# EEZ_DIB_AFE3_r1B2.net
KiCad netlist of a schematic drawn in EAGLE
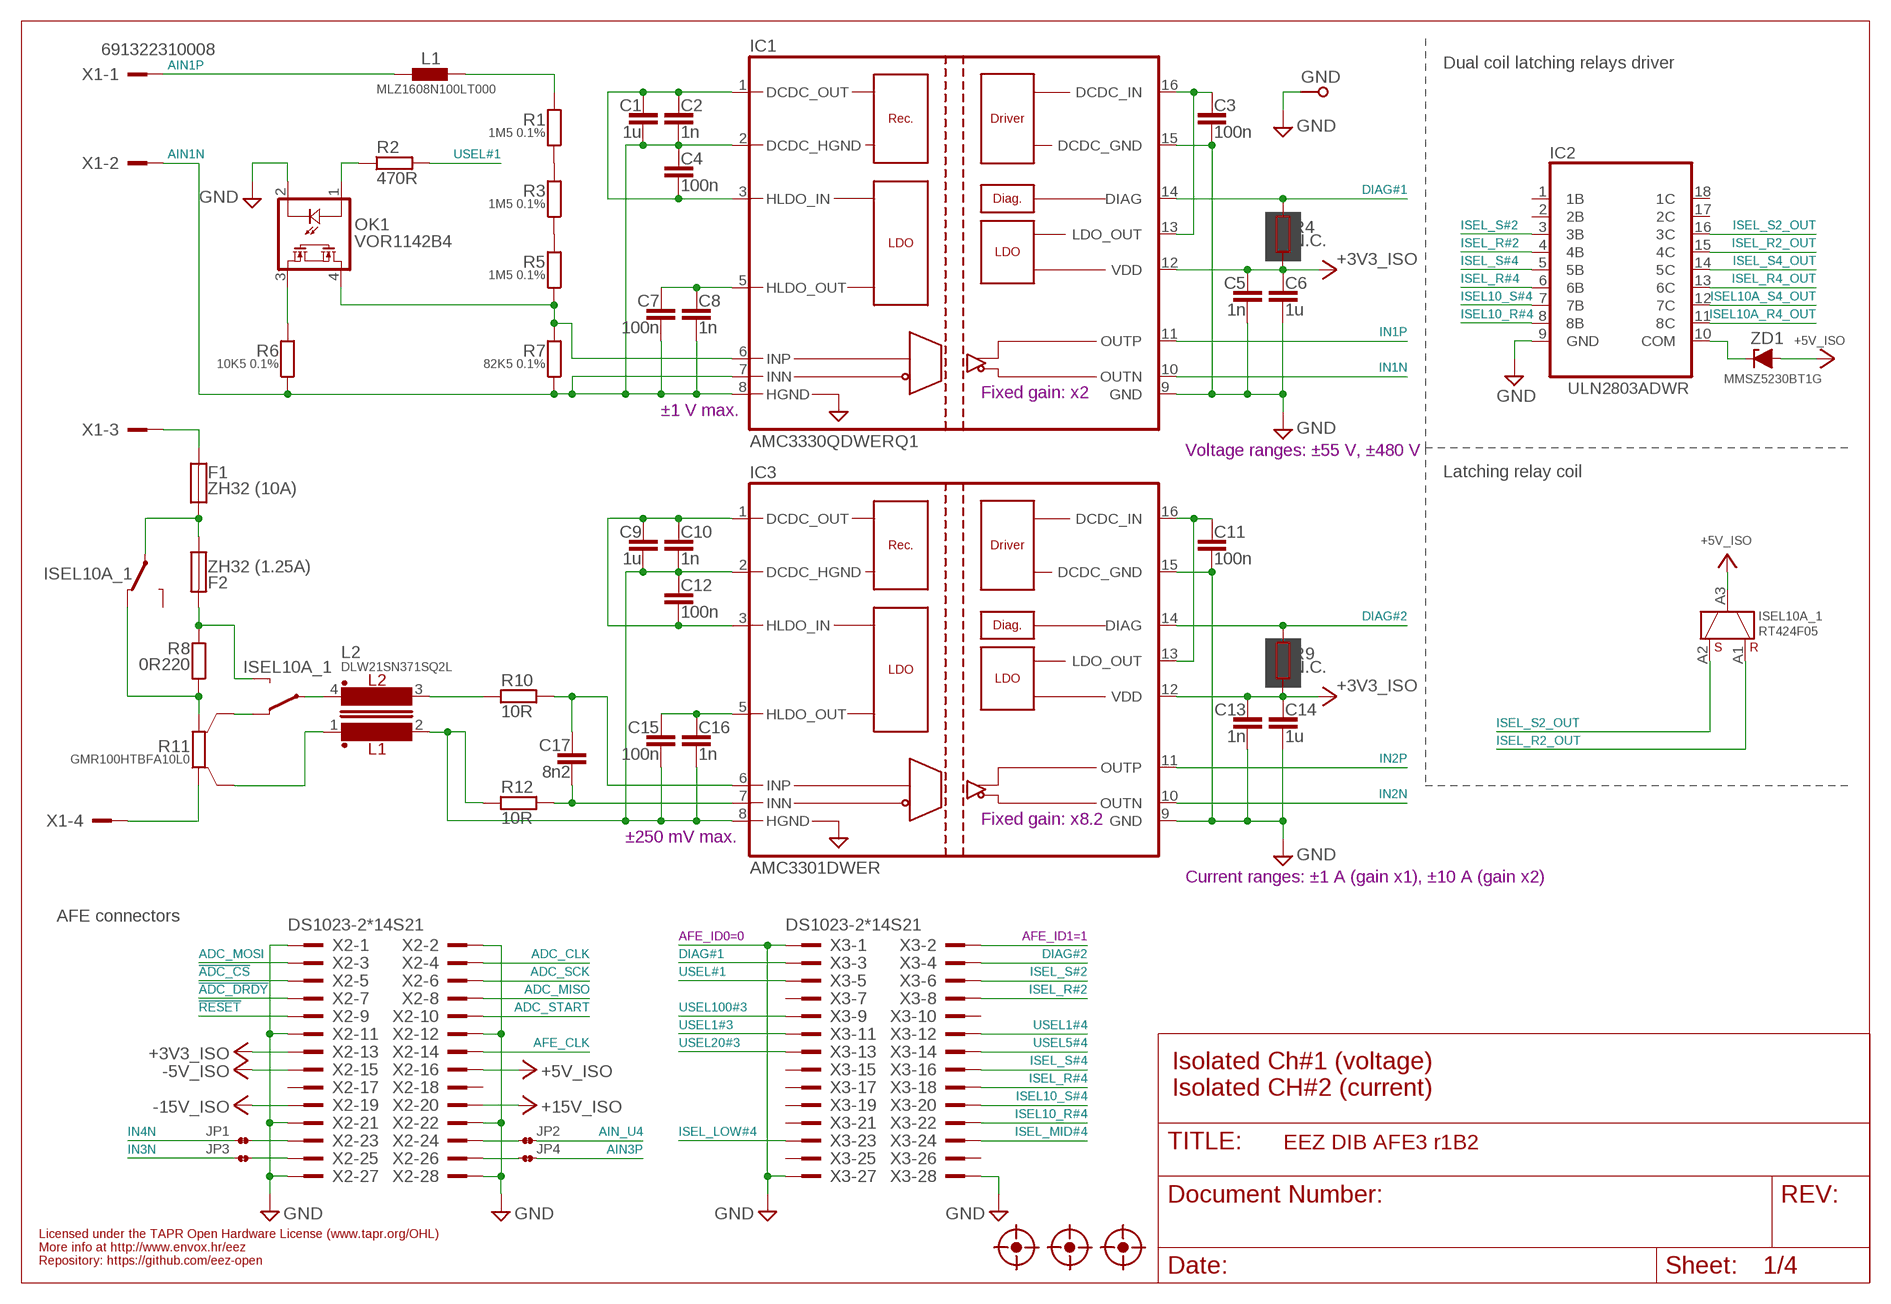
[diagram p0: schematic, sheet 1]
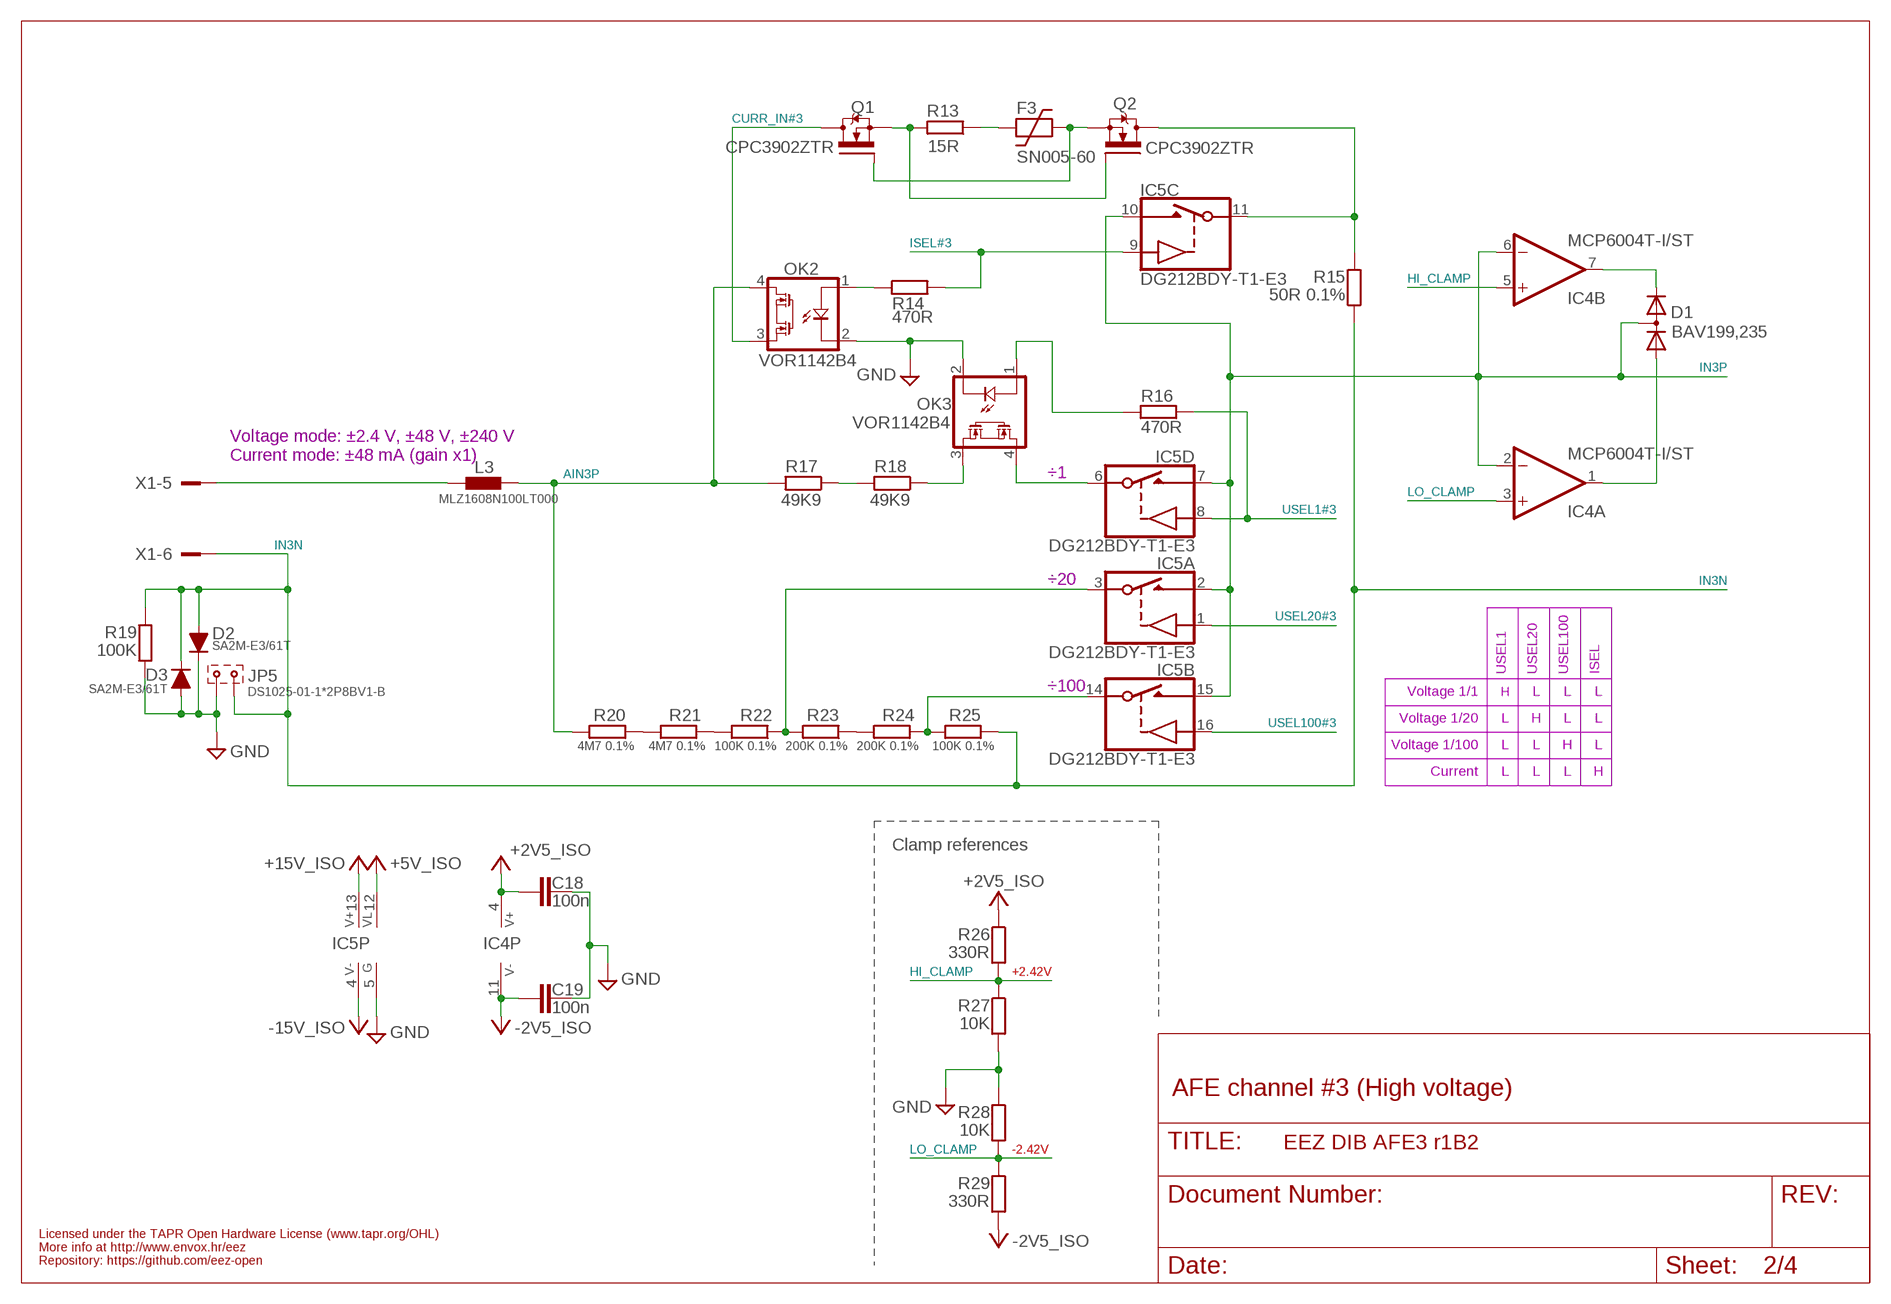
[diagram p1: schematic, sheet 2]
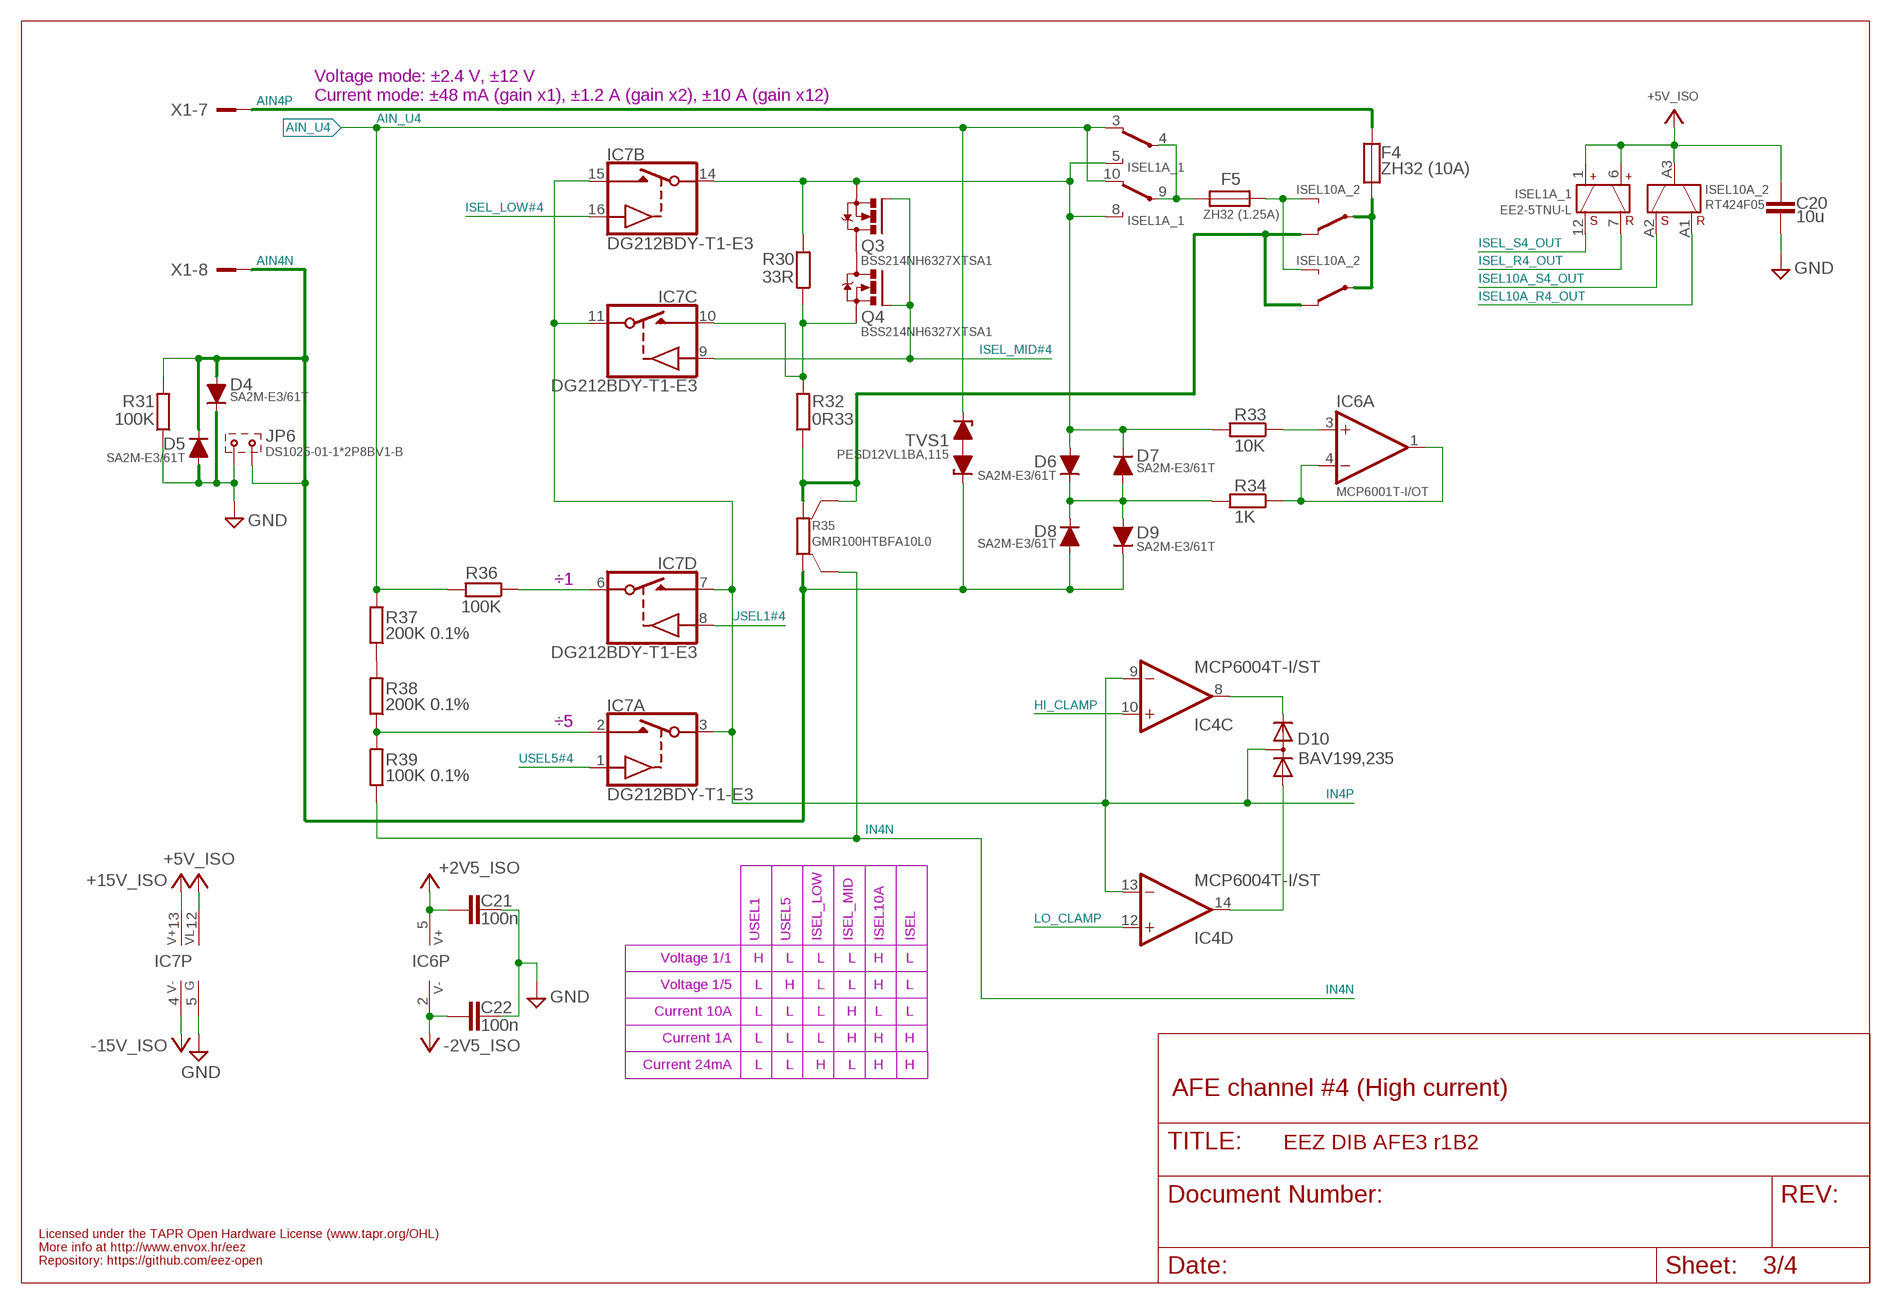
[diagram p2: schematic, sheet 3]
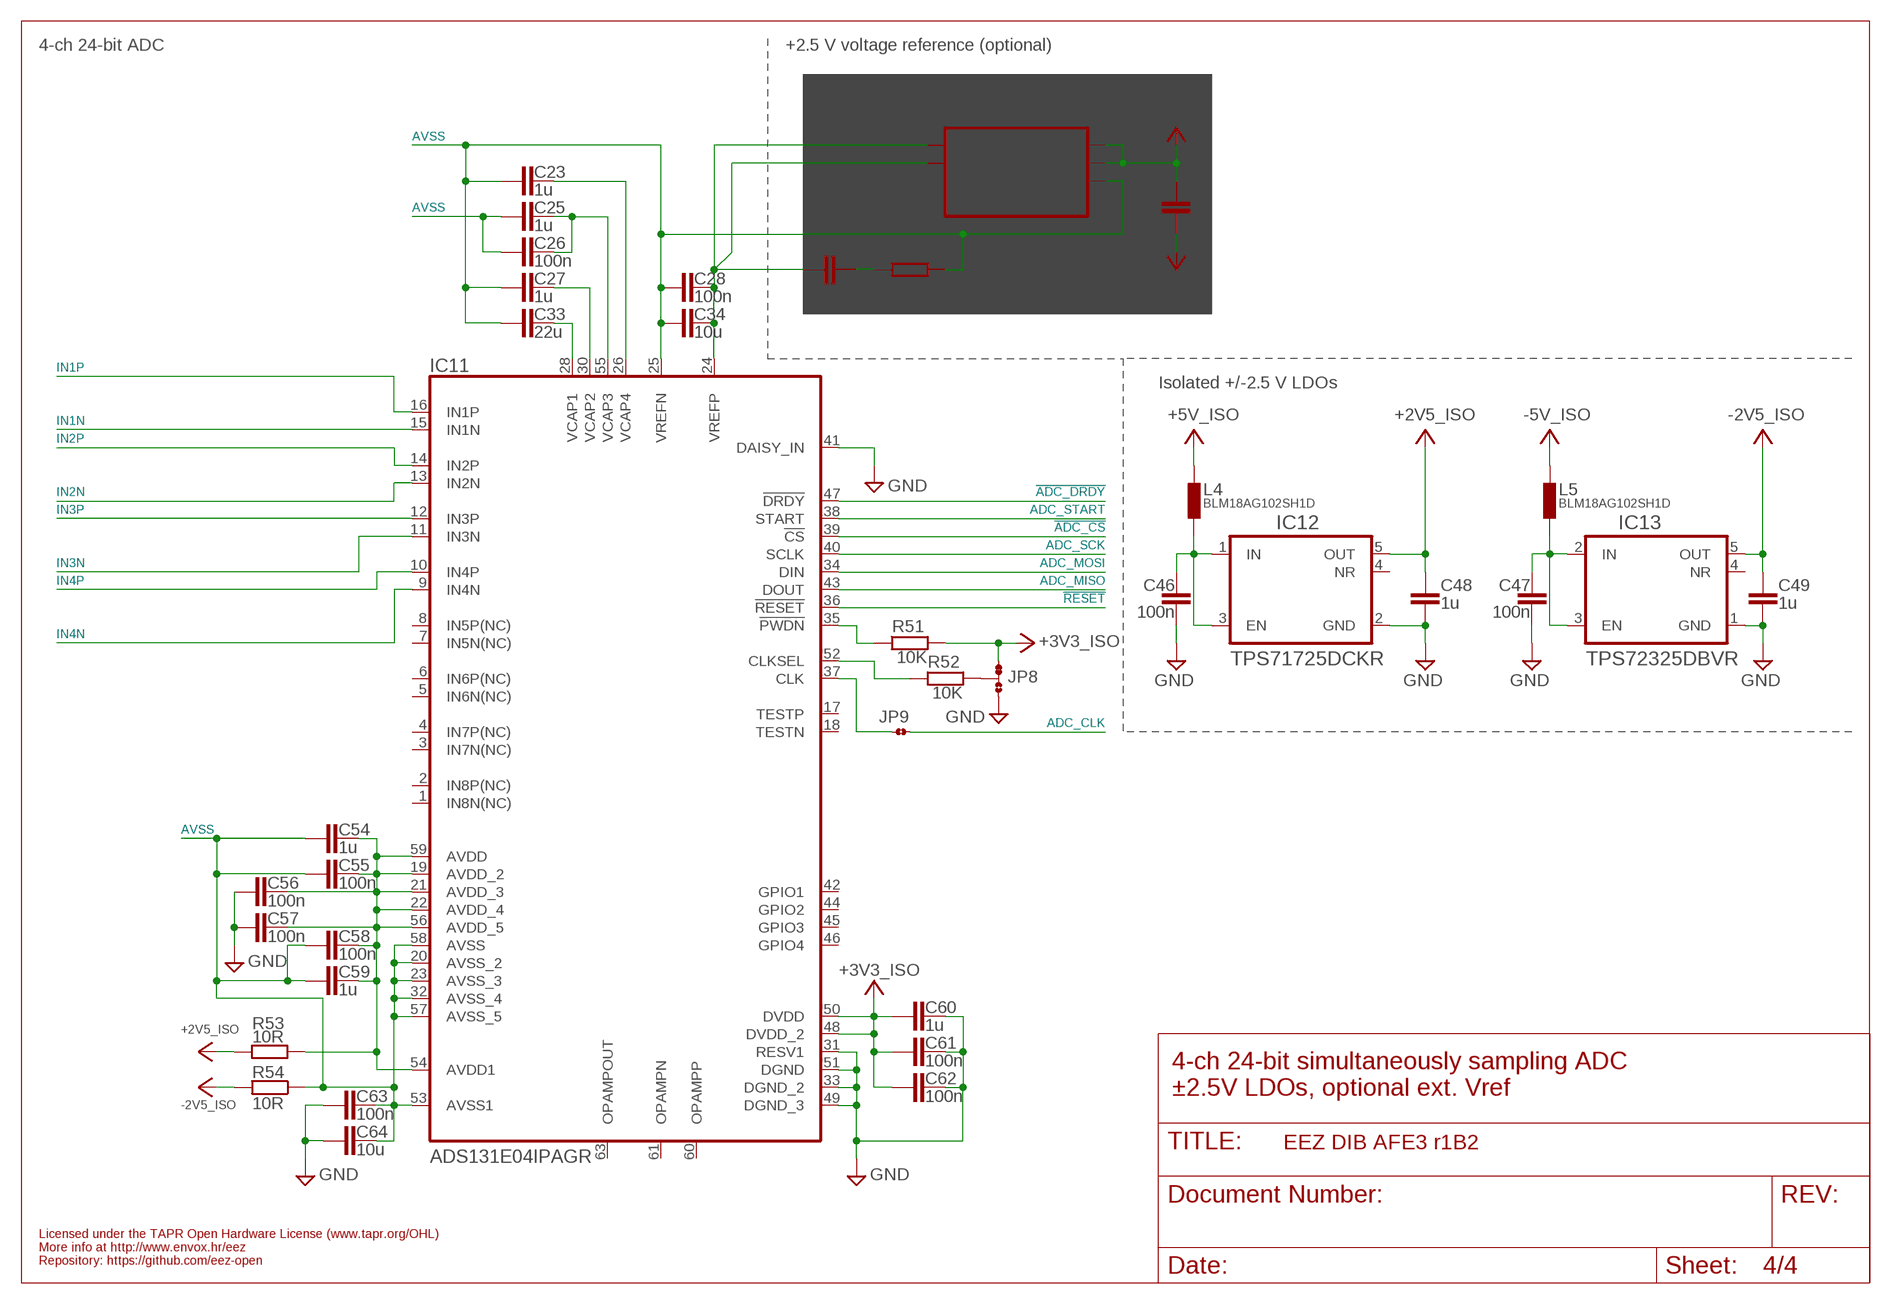
[diagram p3: schematic, sheet 4]

(export (version "E")
  (design (tool "Eeschema 10.0.6"))
  (components
    (comp (ref "C18")
      (value "100n")
      (footprint "eagle-import:C0603")
      (libsource (lib "eagle-import") (part "C-EUC0603"))
    )
    (comp (ref "C19")
      (value "100n")
      (footprint "eagle-import:C0603")
      (libsource (lib "eagle-import") (part "C-EUC0603"))
    )
    (comp (ref "D1")
      (value "BAV199,235")
      (footprint "eagle-import:SOT23")
      (libsource (lib "eagle-import") (part "BAV199"))
    )
    (comp (ref "D2")
      (value "SA2M-E3/61T")
      (footprint "eagle-import:SMA_NARROW")
      (libsource (lib "eagle-import") (part "DIODE_SMA-NARROW"))
    )
    (comp (ref "D3")
      (value "SA2M-E3/61T")
      (footprint "eagle-import:SMA_NARROW")
      (libsource (lib "eagle-import") (part "DIODE_SMA-NARROW"))
    )
    (comp (ref "F3")
      (value "SN005-60")
      (footprint "eagle-import:C1206-HV")
      (libsource (lib "eagle-import") (part "FUSE_RESETTABLE2"))
    )
    (comp (ref "IC4")
      (value "MCP6004T-I/ST")
      (footprint "eagle-import:PW(R-PDSO-G14)")
      (libsource (lib "eagle-import") (part "OPA4197PW"))
    )
    (comp (ref "IC5")
      (value "DG212BDY-T1-E3")
      (footprint "eagle-import:SO16")
      (libsource (lib "eagle-import") (part "DG212BDY-T1-E3"))
    )
    (comp (ref "JP5")
      (value "DS1025-01-1*2P8BV1-B")
      (footprint "eagle-import:2MM-2")
      (libsource (lib "eagle-import") (part "JUMPER-2PIN-2MM"))
    )
    (comp (ref "L3")
      (value "MLZ1608N100LT000")
      (footprint "eagle-import:BEAD0603")
      (libsource (lib "eagle-import") (part "FERRITE_BEAD0603"))
    )
    (comp (ref "OK2")
      (value "VOR1142B4")
      (footprint "eagle-import:DIL4-SMD")
      (libsource (lib "eagle-import") (part "VOR1142B4"))
    )
    (comp (ref "OK3")
      (value "VOR1142B4")
      (footprint "eagle-import:DIL4-SMD")
      (libsource (lib "eagle-import") (part "VOR1142B4"))
    )
    (comp (ref "Q1")
      (value "CPC3902ZTR")
      (footprint "eagle-import:SOT230P700X180-4N")
      (libsource (lib "eagle-import") (part "BSP129SOT-223"))
    )
    (comp (ref "Q2")
      (value "CPC3902ZTR")
      (footprint "eagle-import:SOT230P700X180-4N")
      (libsource (lib "eagle-import") (part "BSP129SOT-223"))
    )
    (comp (ref "R13")
      (value "15R")
      (footprint "eagle-import:R0805")
      (libsource (lib "eagle-import") (part "R-EU_R0805"))
    )
    (comp (ref "R14")
      (value "470R")
      (footprint "eagle-import:R0805")
      (libsource (lib "eagle-import") (part "R-EU_R0805"))
    )
    (comp (ref "R15")
      (value "50R 0.1%")
      (footprint "eagle-import:R1206")
      (libsource (lib "eagle-import") (part "R-EU_R1206"))
    )
    (comp (ref "R16")
      (value "470R")
      (footprint "eagle-import:R0805")
      (libsource (lib "eagle-import") (part "R-EU_R0805"))
    )
    (comp (ref "R17")
      (value "49K9")
      (footprint "eagle-import:R1206")
      (libsource (lib "eagle-import") (part "R-EU_R1206"))
    )
    (comp (ref "R18")
      (value "49K9")
      (footprint "eagle-import:R1206")
      (libsource (lib "eagle-import") (part "R-EU_R1206"))
    )
    (comp (ref "R19")
      (value "100K")
      (footprint "eagle-import:R1206")
      (libsource (lib "eagle-import") (part "R-EU_R1206"))
    )
    (comp (ref "R20")
      (value "4M7 0.1%")
      (footprint "eagle-import:R1206")
      (libsource (lib "eagle-import") (part "R-EU_R1206"))
    )
    (comp (ref "R21")
      (value "4M7 0.1%")
      (footprint "eagle-import:R1206")
      (libsource (lib "eagle-import") (part "R-EU_R1206"))
    )
    (comp (ref "R22")
      (value "100K 0.1%")
      (footprint "eagle-import:R1206")
      (libsource (lib "eagle-import") (part "R-EU_R1206"))
    )
    (comp (ref "R23")
      (value "200K 0.1%")
      (footprint "eagle-import:R1206")
      (libsource (lib "eagle-import") (part "R-EU_R1206"))
    )
    (comp (ref "R24")
      (value "200K 0.1%")
      (footprint "eagle-import:R1206")
      (libsource (lib "eagle-import") (part "R-EU_R1206"))
    )
    (comp (ref "R25")
      (value "100K 0.1%")
      (footprint "eagle-import:R1206")
      (libsource (lib "eagle-import") (part "R-EU_R1206"))
    )
    (comp (ref "R26")
      (value "330R")
      (footprint "eagle-import:R0805")
      (libsource (lib "eagle-import") (part "R-EU_R0805"))
    )
    (comp (ref "R27")
      (value "10K")
      (footprint "eagle-import:R0805")
      (libsource (lib "eagle-import") (part "R-EU_R0805"))
    )
    (comp (ref "R28")
      (value "10K")
      (footprint "eagle-import:R0805")
      (libsource (lib "eagle-import") (part "R-EU_R0805"))
    )
    (comp (ref "R29")
      (value "330R")
      (footprint "eagle-import:R0805")
      (libsource (lib "eagle-import") (part "R-EU_R0805"))
    )
    (comp (ref "X1")
      (value "691322310008")
      (footprint "eagle-import:691322310008")
      (libsource (lib "eagle-import") (part "691322310008"))
    )
    (comp (ref "C23")
      (value "1u")
      (footprint "eagle-import:C0805")
      (libsource (lib "eagle-import") (part "C-EUC0805"))
    )
    (comp (ref "C24")
      (value "N.C.")
      (footprint "eagle-import:C1206")
      (libsource (lib "eagle-import") (part "C-EUC1206"))
    )
    (comp (ref "C25")
      (value "1u")
      (footprint "eagle-import:C0805")
      (libsource (lib "eagle-import") (part "C-EUC0805"))
    )
    (comp (ref "C26")
      (value "100n")
      (footprint "eagle-import:C0603")
      (libsource (lib "eagle-import") (part "C-EUC0603"))
    )
    (comp (ref "C27")
      (value "1u")
      (footprint "eagle-import:C0805")
      (libsource (lib "eagle-import") (part "C-EUC0805"))
    )
    (comp (ref "C28")
      (value "100n")
      (footprint "eagle-import:C0603")
      (libsource (lib "eagle-import") (part "C-EUC0603"))
    )
    (comp (ref "C33")
      (value "22u")
      (footprint "eagle-import:C1206")
      (libsource (lib "eagle-import") (part "C-EUC1206"))
    )
    (comp (ref "C34")
      (value "10u")
      (footprint "eagle-import:C1206")
      (libsource (lib "eagle-import") (part "C-EUC1206"))
    )
    (comp (ref "C35")
      (value "N.C.")
      (footprint "eagle-import:C1206")
      (libsource (lib "eagle-import") (part "C-EUC1206"))
    )
    (comp (ref "C46")
      (value "100n")
      (footprint "eagle-import:C0603")
      (libsource (lib "eagle-import") (part "C-EUC0603"))
    )
    (comp (ref "C47")
      (value "100n")
      (footprint "eagle-import:C0603")
      (libsource (lib "eagle-import") (part "C-EUC0603"))
    )
    (comp (ref "C48")
      (value "1u")
      (footprint "eagle-import:C0805")
      (libsource (lib "eagle-import") (part "C-EUC0805"))
    )
    (comp (ref "C49")
      (value "1u")
      (footprint "eagle-import:C0805")
      (libsource (lib "eagle-import") (part "C-EUC0805"))
    )
    (comp (ref "C54")
      (value "1u")
      (footprint "eagle-import:C0805")
      (libsource (lib "eagle-import") (part "C-EUC0805"))
    )
    (comp (ref "C55")
      (value "100n")
      (footprint "eagle-import:C0603")
      (libsource (lib "eagle-import") (part "C-EUC0603"))
    )
    (comp (ref "C56")
      (value "100n")
      (footprint "eagle-import:C0603")
      (libsource (lib "eagle-import") (part "C-EUC0603"))
    )
    (comp (ref "C57")
      (value "100n")
      (footprint "eagle-import:C0603")
      (libsource (lib "eagle-import") (part "C-EUC0603"))
    )
    (comp (ref "C58")
      (value "100n")
      (footprint "eagle-import:C0603")
      (libsource (lib "eagle-import") (part "C-EUC0603"))
    )
    (comp (ref "C59")
      (value "1u")
      (footprint "eagle-import:C0805")
      (libsource (lib "eagle-import") (part "C-EUC0805"))
    )
    (comp (ref "C60")
      (value "1u")
      (footprint "eagle-import:C0805")
      (libsource (lib "eagle-import") (part "C-EUC0805"))
    )
    (comp (ref "C61")
      (value "100n")
      (footprint "eagle-import:C0603")
      (libsource (lib "eagle-import") (part "C-EUC0603"))
    )
    (comp (ref "C62")
      (value "100n")
      (footprint "eagle-import:C0603")
      (libsource (lib "eagle-import") (part "C-EUC0603"))
    )
    (comp (ref "C63")
      (value "100n")
      (footprint "eagle-import:C0603")
      (libsource (lib "eagle-import") (part "C-EUC0603"))
    )
    (comp (ref "C64")
      (value "10u")
      (footprint "eagle-import:C1206")
      (libsource (lib "eagle-import") (part "C-EUC1206"))
    )
    (comp (ref "IC8")
      (value "N.C.")
      (footprint "eagle-import:MSOP-8_MS_LIT")
      (libsource (lib "eagle-import") (part "LTC6655BHMS8"))
    )
    (comp (ref "IC11")
      (value "ADS131E04IPAGR")
      (footprint "eagle-import:PAG64")
      (libsource (lib "eagle-import") (part "ADS131E0XIPAG"))
    )
    (comp (ref "IC12")
      (value "TPS71725DCKR")
      (footprint "eagle-import:DCK5")
      (libsource (lib "eagle-import") (part "TPS71725DCKR"))
    )
    (comp (ref "IC13")
      (value "TPS72325DBVR")
      (footprint "eagle-import:DBV5")
      (libsource (lib "eagle-import") (part "TPS72325DBVR"))
    )
    (comp (ref "JP8")
      (value "JP3-CUT-0805-ROTATED")
      (footprint "eagle-import:JP3-0805-CUT2")
      (libsource (lib "eagle-import") (part "JP3-CUT-0805-ROTATED"))
    )
    (comp (ref "JP9")
      (value "JP2-CUT-0805")
      (footprint "eagle-import:R_0805")
      (libsource (lib "eagle-import") (part "JP2-CUT-0805"))
    )
    (comp (ref "L4")
      (value "BLM18AG102SH1D")
      (footprint "eagle-import:BEAD0603")
      (libsource (lib "eagle-import") (part "FERRITE_BEAD0603"))
    )
    (comp (ref "L5")
      (value "BLM18AG102SH1D")
      (footprint "eagle-import:BEAD0603")
      (libsource (lib "eagle-import") (part "FERRITE_BEAD0603"))
    )
    (comp (ref "R51")
      (value "10K")
      (footprint "eagle-import:R0805")
      (libsource (lib "eagle-import") (part "R-EU_R0805"))
    )
    (comp (ref "R52")
      (value "10K")
      (footprint "eagle-import:R0805")
      (libsource (lib "eagle-import") (part "R-EU_R0805"))
    )
    (comp (ref "R53")
      (value "10R")
      (footprint "eagle-import:R0805")
      (libsource (lib "eagle-import") (part "R-EU_R0805"))
    )
    (comp (ref "R54")
      (value "10R")
      (footprint "eagle-import:R0805")
      (libsource (lib "eagle-import") (part "R-EU_R0805"))
    )
    (comp (ref "R65")
      (value "N.C.")
      (footprint "eagle-import:R0805")
      (libsource (lib "eagle-import") (part "R-EU_R0805"))
    )
    (comp (ref "C20")
      (value "10u")
      (footprint "eagle-import:C1206")
      (libsource (lib "eagle-import") (part "C-EUC1206"))
    )
    (comp (ref "C21")
      (value "100n")
      (footprint "eagle-import:C0603")
      (libsource (lib "eagle-import") (part "C-EUC0603"))
    )
    (comp (ref "C22")
      (value "100n")
      (footprint "eagle-import:C0603")
      (libsource (lib "eagle-import") (part "C-EUC0603"))
    )
    (comp (ref "D4")
      (value "SA2M-E3/61T")
      (footprint "eagle-import:SMA_NARROW")
      (libsource (lib "eagle-import") (part "DIODE_SMA-NARROW"))
    )
    (comp (ref "D5")
      (value "SA2M-E3/61T")
      (footprint "eagle-import:SMA_NARROW")
      (libsource (lib "eagle-import") (part "DIODE_SMA-NARROW"))
    )
    (comp (ref "D6")
      (value "SA2M-E3/61T")
      (footprint "eagle-import:SMA_NARROW")
      (libsource (lib "eagle-import") (part "DIODE_SMA-NARROW"))
    )
    (comp (ref "D7")
      (value "SA2M-E3/61T")
      (footprint "eagle-import:SMA_NARROW")
      (libsource (lib "eagle-import") (part "DIODE_SMA-NARROW"))
    )
    (comp (ref "D8")
      (value "SA2M-E3/61T")
      (footprint "eagle-import:SMA_NARROW")
      (libsource (lib "eagle-import") (part "DIODE_SMA-NARROW"))
    )
    (comp (ref "D9")
      (value "SA2M-E3/61T")
      (footprint "eagle-import:SMA_NARROW")
      (libsource (lib "eagle-import") (part "DIODE_SMA-NARROW"))
    )
    (comp (ref "D10")
      (value "BAV199,235")
      (footprint "eagle-import:SOT23")
      (libsource (lib "eagle-import") (part "BAV199"))
    )
    (comp (ref "F4")
      (value "ZH32 (10A)")
      (footprint "eagle-import:ZH32")
      (libsource (lib "eagle-import") (part "ZH32"))
    )
    (comp (ref "F5")
      (value "ZH32 (1.25A)")
      (footprint "eagle-import:ZH32")
      (libsource (lib "eagle-import") (part "ZH32"))
    )
    (comp (ref "IC6")
      (value "MCP6001T-I/OT")
      (footprint "eagle-import:DBV5")
      (libsource (lib "eagle-import") (part "OPA376AIDBVR"))
    )
    (comp (ref "IC7")
      (value "DG212BDY-T1-E3")
      (footprint "eagle-import:SO16")
      (libsource (lib "eagle-import") (part "DG212BDY-T1-E3"))
    )
    (comp (ref "ISEL1A_1")
      (value "EE2-5TNU-L")
      (footprint "eagle-import:G6SK-2F")
      (libsource (lib "eagle-import") (part "G6SK-2F"))
    )
    (comp (ref "ISEL10A_2")
      (value "RT424F05")
      (footprint "eagle-import:RT424FXX")
      (libsource (lib "eagle-import") (part "RT424FXX"))
    )
    (comp (ref "JP6")
      (value "DS1025-01-1*2P8BV1-B")
      (footprint "eagle-import:2MM-2")
      (libsource (lib "eagle-import") (part "JUMPER-2PIN-2MM"))
    )
    (comp (ref "Q3")
      (value "BSS214NH6327XTSA1")
      (footprint "eagle-import:SOT103P240X110-3N")
      (fields
        (field (name "MPN") "2N7002-7-F")
        (field (name "MPN_1") "2N7002-7-F")
        (field (name "OC_FARNELL") "1713823")
        (field (name "OC_NEWARK") "25R5679")
        (field (name "PACKAGE") "SOT-23-3")
        (field (name "SUPPLIER") "DIODES INC.")
      )
      (libsource (lib "eagle-import") (part "2N7002"))
    )
    (comp (ref "Q4")
      (value "BSS214NH6327XTSA1")
      (footprint "eagle-import:SOT103P240X110-3N")
      (fields (field (name "MPN") "2N7002-7-F"))
      (libsource (lib "eagle-import") (part "2N7002"))
    )
    (comp (ref "R30")
      (value "33R")
      (footprint "eagle-import:R1206")
      (libsource (lib "eagle-import") (part "R-EU_R1206"))
    )
    (comp (ref "R31")
      (value "100K")
      (footprint "eagle-import:R1206")
      (libsource (lib "eagle-import") (part "R-EU_R1206"))
    )
    (comp (ref "R32")
      (value "0R33")
      (footprint "eagle-import:R1210")
      (libsource (lib "eagle-import") (part "R-EU_R1210"))
    )
    (comp (ref "R33")
      (value "10K")
      (footprint "eagle-import:R0805")
      (libsource (lib "eagle-import") (part "R-EU_R0805"))
    )
    (comp (ref "R34")
      (value "1K")
      (footprint "eagle-import:R0805")
      (libsource (lib "eagle-import") (part "R-EU_R0805"))
    )
    (comp (ref "R35")
      (value "GMR100HTBFA10L0")
      (footprint "eagle-import:R_2512-4WIRE")
      (libsource (lib "eagle-import") (part "R-EU_4WIRE2512"))
    )
    (comp (ref "R36")
      (value "100K")
      (footprint "eagle-import:R1206")
      (libsource (lib "eagle-import") (part "R-EU_R1206"))
    )
    (comp (ref "R37")
      (value "200K 0.1%")
      (footprint "eagle-import:R1206")
      (libsource (lib "eagle-import") (part "R-EU_R1206"))
    )
    (comp (ref "R38")
      (value "200K 0.1%")
      (footprint "eagle-import:R1206")
      (libsource (lib "eagle-import") (part "R-EU_R1206"))
    )
    (comp (ref "R39")
      (value "100K 0.1%")
      (footprint "eagle-import:R1206")
      (libsource (lib "eagle-import") (part "R-EU_R1206"))
    )
    (comp (ref "TVS1")
      (value "PESD12VL1BA,115")
      (footprint "eagle-import:SOD323-BIDIR")
      (libsource (lib "eagle-import") (part "PESDXL1BA"))
    )
    (comp (ref "C1")
      (value "1u")
      (footprint "eagle-import:C0603")
      (libsource (lib "eagle-import") (part "C-EUC0603"))
    )
    (comp (ref "C2")
      (value "1n")
      (footprint "eagle-import:C0603")
      (libsource (lib "eagle-import") (part "C-EUC0603"))
    )
    (comp (ref "C3")
      (value "100n")
      (footprint "eagle-import:C0603")
      (libsource (lib "eagle-import") (part "C-EUC0603"))
    )
    (comp (ref "C4")
      (value "100n")
      (footprint "eagle-import:C0603")
      (libsource (lib "eagle-import") (part "C-EUC0603"))
    )
    (comp (ref "C5")
      (value "1n")
      (footprint "eagle-import:C1206")
      (libsource (lib "eagle-import") (part "C-EUC1206"))
    )
    (comp (ref "C6")
      (value "1u")
      (footprint "eagle-import:C1206")
      (libsource (lib "eagle-import") (part "C-EUC1206"))
    )
    (comp (ref "C7")
      (value "100n")
      (footprint "eagle-import:C1206")
      (libsource (lib "eagle-import") (part "C-EUC1206"))
    )
    (comp (ref "C8")
      (value "1n")
      (footprint "eagle-import:C1206")
      (libsource (lib "eagle-import") (part "C-EUC1206"))
    )
    (comp (ref "C9")
      (value "1u")
      (footprint "eagle-import:C0603")
      (libsource (lib "eagle-import") (part "C-EUC0603"))
    )
    (comp (ref "C10")
      (value "1n")
      (footprint "eagle-import:C0603")
      (libsource (lib "eagle-import") (part "C-EUC0603"))
    )
    (comp (ref "C11")
      (value "100n")
      (footprint "eagle-import:C0603")
      (libsource (lib "eagle-import") (part "C-EUC0603"))
    )
    (comp (ref "C12")
      (value "100n")
      (footprint "eagle-import:C0603")
      (libsource (lib "eagle-import") (part "C-EUC0603"))
    )
    (comp (ref "C13")
      (value "1n")
      (footprint "eagle-import:C1206")
      (libsource (lib "eagle-import") (part "C-EUC1206"))
    )
    (comp (ref "C14")
      (value "1u")
      (footprint "eagle-import:C1206")
      (libsource (lib "eagle-import") (part "C-EUC1206"))
    )
    (comp (ref "C15")
      (value "100n")
      (footprint "eagle-import:C1206")
      (libsource (lib "eagle-import") (part "C-EUC1206"))
    )
    (comp (ref "C16")
      (value "1n")
      (footprint "eagle-import:C1206")
      (libsource (lib "eagle-import") (part "C-EUC1206"))
    )
    (comp (ref "C17")
      (value "8n2")
      (footprint "eagle-import:C0603")
      (libsource (lib "eagle-import") (part "C-EUC0603"))
    )
    (comp (ref "F1")
      (value "ZH32 (10A)")
      (footprint "eagle-import:ZH32")
      (libsource (lib "eagle-import") (part "ZH32"))
    )
    (comp (ref "F2")
      (value "ZH32 (1.25A)")
      (footprint "eagle-import:ZH32")
      (libsource (lib "eagle-import") (part "ZH32"))
    )
    (comp (ref "FM1")
      (value "FIDUCIAL_2")
      (footprint "eagle-import:FIDUCIAL_DUAL")
      (libsource (lib "eagle-import") (part "FIDUCIAL_2"))
    )
    (comp (ref "FM2")
      (value "FIDUCIAL_2")
      (footprint "eagle-import:FIDUCIAL_DUAL")
      (libsource (lib "eagle-import") (part "FIDUCIAL_2"))
    )
    (comp (ref "FM3")
      (value "FIDUCIAL_2")
      (footprint "eagle-import:FIDUCIAL_DUAL")
      (libsource (lib "eagle-import") (part "FIDUCIAL_2"))
    )
    (comp (ref "GND")
      (value "PCB_TEST_TABSHIELD")
      (footprint "eagle-import:PCB_SHIELD_TAB")
      (libsource (lib "eagle-import") (part "PCB_TEST_TABSHIELD"))
    )
    (comp (ref "IC1")
      (value "AMC3330QDWERQ1")
      (footprint "eagle-import:DW16")
      (libsource (lib "eagle-import") (part "AMC3301DWER"))
    )
    (comp (ref "IC2")
      (value "ULN2803ADWR")
      (footprint "eagle-import:DW18_TEX-M")
      (libsource (lib "eagle-import") (part "ULN2803ADWR"))
    )
    (comp (ref "IC3")
      (value "AMC3301DWER")
      (footprint "eagle-import:DW16")
      (libsource (lib "eagle-import") (part "AMC3301DWER"))
    )
    (comp (ref "ISEL10A_1")
      (value "RT424F05")
      (footprint "eagle-import:RT424FXX")
      (libsource (lib "eagle-import") (part "RT424FXX"))
    )
    (comp (ref "JP1")
      (value "JP2-NOCUT-0805")
      (footprint "eagle-import:JP2-0805-NOCUT")
      (libsource (lib "eagle-import") (part "JP2-NOCUT-0805"))
    )
    (comp (ref "JP2")
      (value "JP2-NOCUT-0805")
      (footprint "eagle-import:JP2-0805-NOCUT")
      (libsource (lib "eagle-import") (part "JP2-NOCUT-0805"))
    )
    (comp (ref "JP3")
      (value "JP2-NOCUT-0805")
      (footprint "eagle-import:JP2-0805-NOCUT")
      (libsource (lib "eagle-import") (part "JP2-NOCUT-0805"))
    )
    (comp (ref "JP4")
      (value "JP2-NOCUT-0805")
      (footprint "eagle-import:JP2-0805-NOCUT")
      (libsource (lib "eagle-import") (part "JP2-NOCUT-0805"))
    )
    (comp (ref "L1")
      (value "MLZ1608N100LT000")
      (footprint "eagle-import:BEAD0603")
      (libsource (lib "eagle-import") (part "FERRITE_BEAD0603"))
    )
    (comp (ref "L2")
      (value "DLW21SN371SQ2L")
      (footprint "eagle-import:MURATA_DLW21S")
      (libsource (lib "eagle-import") (part "DLW21S"))
    )
    (comp (ref "OK1")
      (value "VOR1142B4")
      (footprint "eagle-import:DIL4-SMD")
      (libsource (lib "eagle-import") (part "VOR1142B4"))
    )
    (comp (ref "R1")
      (value "1M5 0.1%")
      (footprint "eagle-import:R1206")
      (libsource (lib "eagle-import") (part "R-EU_R1206"))
    )
    (comp (ref "R2")
      (value "470R")
      (footprint "eagle-import:R0805")
      (libsource (lib "eagle-import") (part "R-EU_R0805"))
    )
    (comp (ref "R3")
      (value "1M5 0.1%")
      (footprint "eagle-import:R1206")
      (libsource (lib "eagle-import") (part "R-EU_R1206"))
    )
    (comp (ref "R4")
      (value "N.C.")
      (footprint "eagle-import:R0805")
      (libsource (lib "eagle-import") (part "R-EU_R0805"))
    )
    (comp (ref "R5")
      (value "1M5 0.1%")
      (footprint "eagle-import:R1206")
      (libsource (lib "eagle-import") (part "R-EU_R1206"))
    )
    (comp (ref "R6")
      (value "10K5 0.1%")
      (footprint "eagle-import:R1206")
      (libsource (lib "eagle-import") (part "R-EU_R1206"))
    )
    (comp (ref "R7")
      (value "82K5 0.1%")
      (footprint "eagle-import:R1206")
      (libsource (lib "eagle-import") (part "R-EU_R1206"))
    )
    (comp (ref "R8")
      (value "0R220")
      (footprint "eagle-import:R1210")
      (libsource (lib "eagle-import") (part "R-EU_R1210"))
    )
    (comp (ref "R9")
      (value "N.C.")
      (footprint "eagle-import:R0805")
      (libsource (lib "eagle-import") (part "R-EU_R0805"))
    )
    (comp (ref "R10")
      (value "10R")
      (footprint "eagle-import:R0805")
      (libsource (lib "eagle-import") (part "R-EU_R0805"))
    )
    (comp (ref "R11")
      (value "GMR100HTBFA10L0")
      (footprint "eagle-import:R_2512-4WIRE")
      (libsource (lib "eagle-import") (part "R-EU_4WIRE2512"))
    )
    (comp (ref "R12")
      (value "10R")
      (footprint "eagle-import:R0805")
      (libsource (lib "eagle-import") (part "R-EU_R0805"))
    )
    (comp (ref "X2")
      (value "DS1023-2*14S21")
      (footprint "eagle-import:TSW-114-07-F-D")
      (libsource (lib "eagle-import") (part "TSW-114-07-F-D"))
    )
    (comp (ref "X3")
      (value "DS1023-2*14S21")
      (footprint "eagle-import:TSW-114-07-F-D")
      (libsource (lib "eagle-import") (part "TSW-114-07-F-D"))
    )
    (comp (ref "ZD1")
      (value "MMSZ5230BT1G")
      (footprint "eagle-import:SOD123")
      (libsource (lib "eagle-import") (part "ZENER-DIODESOD123"))
    )
  )
  (nets
    (net (code "1") (name "+2V5_ISO") (class "Default")
      (node (ref "C18") (pin "2") (pinfunction "2_2") (pintype "passive"))
      (node (ref "C21") (pin "2") (pinfunction "2_2") (pintype "passive"))
      (node (ref "C48") (pin "2") (pinfunction "2_2") (pintype "passive"))
      (node (ref "IC12") (pin "5") (pinfunction "OUT_5") (pintype "passive"))
      (node (ref "IC4") (pin "4") (pinfunction "V+_4") (pintype "power_in"))
      (node (ref "IC6") (pin "5") (pinfunction "V+_5") (pintype "power_in"))
      (node (ref "R26") (pin "1") (pinfunction "1_1") (pintype "passive"))
      (node (ref "R53") (pin "1") (pinfunction "1_1") (pintype "passive"))
    )
    (net (code "2") (name "+3V3_ISO") (class "Default")
      (node (ref "C13") (pin "1") (pinfunction "1_1") (pintype "passive"))
      (node (ref "C14") (pin "1") (pinfunction "1_1") (pintype "passive"))
      (node (ref "C5") (pin "1") (pinfunction "1_1") (pintype "passive"))
      (node (ref "C6") (pin "1") (pinfunction "1_1") (pintype "passive"))
      (node (ref "C60") (pin "1") (pinfunction "1_1") (pintype "passive"))
      (node (ref "C61") (pin "2") (pinfunction "2_2") (pintype "passive"))
      (node (ref "C62") (pin "2") (pinfunction "2_2") (pintype "passive"))
      (node (ref "IC1") (pin "12") (pinfunction "VDD_12") (pintype "passive"))
      (node (ref "IC11") (pin "48") (pinfunction "DVDD_2_48") (pintype "power_in"))
      (node (ref "IC11") (pin "50") (pinfunction "DVDD_50") (pintype "power_in"))
      (node (ref "IC3") (pin "12") (pinfunction "VDD_12") (pintype "passive"))
      (node (ref "JP8") (pin "NC") (pinfunction "NC_NC") (pintype "passive"))
      (node (ref "R4") (pin "2") (pinfunction "2_2") (pintype "passive"))
      (node (ref "R51") (pin "2") (pinfunction "2_2") (pintype "passive"))
      (node (ref "R9") (pin "2") (pinfunction "2_2") (pintype "passive"))
      (node (ref "X2") (pin "13") (pinfunction "1_13") (pintype "passive"))
    )
    (net (code "3") (name "+5V_ISO") (class "Default")
      (node (ref "C20") (pin "1") (pinfunction "1_1") (pintype "passive"))
      (node (ref "C24") (pin "1") (pinfunction "1_1") (pintype "passive"))
      (node (ref "IC5") (pin "12") (pinfunction "VL_12") (pintype "power_in"))
      (node (ref "IC7") (pin "12") (pinfunction "VL_12") (pintype "power_in"))
      (node (ref "IC8") (pin "1") (pinfunction "~{SHDN}_1") (pintype "input"))
      (node (ref "IC8") (pin "2") (pinfunction "VIN_2") (pintype "input"))
      (node (ref "ISEL10A_1") (pin "A3") (pinfunction "COM_A3") (pintype "passive"))
      (node (ref "ISEL10A_2") (pin "A3") (pinfunction "COM_A3") (pintype "passive"))
      (node (ref "ISEL1A_1") (pin "1") (pinfunction "S+_1") (pintype "passive"))
      (node (ref "ISEL1A_1") (pin "6") (pinfunction "R+_6") (pintype "passive"))
      (node (ref "L4") (pin "P$2") (pinfunction "2_P$2") (pintype "passive"))
      (node (ref "X2") (pin "16") (pinfunction "1_16") (pintype "passive"))
      (node (ref "ZD1") (pin "A") (pinfunction "A_A") (pintype "passive"))
    )
    (net (code "4") (name "+15V_ISO") (class "Default")
      (node (ref "IC5") (pin "13") (pinfunction "V+_13") (pintype "power_in"))
      (node (ref "IC7") (pin "13") (pinfunction "V+_13") (pintype "power_in"))
      (node (ref "X2") (pin "20") (pinfunction "1_20") (pintype "passive"))
    )
    (net (code "5") (name "-2V5_ISO") (class "Default")
      (node (ref "C19") (pin "2") (pinfunction "2_2") (pintype "passive"))
      (node (ref "C22") (pin "2") (pinfunction "2_2") (pintype "passive"))
      (node (ref "C24") (pin "2") (pinfunction "2_2") (pintype "passive"))
      (node (ref "C49") (pin "2") (pinfunction "2_2") (pintype "passive"))
      (node (ref "IC13") (pin "5") (pinfunction "OUT_5") (pintype "passive"))
      (node (ref "IC4") (pin "11") (pinfunction "V-_11") (pintype "power_in"))
      (node (ref "IC6") (pin "2") (pinfunction "V-_2") (pintype "power_in"))
      (node (ref "R29") (pin "2") (pinfunction "2_2") (pintype "passive"))
      (node (ref "R54") (pin "2") (pinfunction "2_2") (pintype "passive"))
    )
    (net (code "6") (name "-5V_ISO") (class "Default")
      (node (ref "L5") (pin "P$2") (pinfunction "2_P$2") (pintype "passive"))
      (node (ref "X2") (pin "15") (pinfunction "1_15") (pintype "passive"))
    )
    (net (code "7") (name "-15V_ISO") (class "Default")
      (node (ref "IC5") (pin "4") (pinfunction "V-_4") (pintype "power_in"))
      (node (ref "IC7") (pin "4") (pinfunction "V-_4") (pintype "power_in"))
      (node (ref "X2") (pin "19") (pinfunction "1_19") (pintype "passive"))
    )
    (net (code "8") (name "ADC_CLK") (class "Default")
      (node (ref "JP9") (pin "1") (pinfunction "1_1") (pintype "passive"))
      (node (ref "X2") (pin "4") (pinfunction "1_4") (pintype "passive"))
    )
    (net (code "9") (name "ADC_MISO") (class "Default")
      (node (ref "IC11") (pin "43") (pinfunction "DOUT_43") (pintype "output"))
      (node (ref "X2") (pin "8") (pinfunction "1_8") (pintype "passive"))
    )
    (net (code "10") (name "ADC_MOSI") (class "Default")
      (node (ref "IC11") (pin "34") (pinfunction "DIN_34") (pintype "input"))
      (node (ref "X2") (pin "3") (pinfunction "1_3") (pintype "passive"))
    )
    (net (code "11") (name "ADC_SCK") (class "Default")
      (node (ref "IC11") (pin "40") (pinfunction "SCLK_40") (pintype "input"))
      (node (ref "X2") (pin "6") (pinfunction "1_6") (pintype "passive"))
    )
    (net (code "12") (name "ADC_START") (class "Default")
      (node (ref "IC11") (pin "38") (pinfunction "START_38") (pintype "input"))
      (node (ref "X2") (pin "10") (pinfunction "1_10") (pintype "passive"))
    )
    (net (code "13") (name "AFE_CLK") (class "Default")
      (node (ref "X2") (pin "14") (pinfunction "1_14") (pintype "passive"))
    )
    (net (code "14") (name "AIN1N") (class "Default")
      (node (ref "C1") (pin "2") (pinfunction "2_2") (pintype "passive"))
      (node (ref "C2") (pin "2") (pinfunction "2_2") (pintype "passive"))
      (node (ref "C4") (pin "1") (pinfunction "1_1") (pintype "passive"))
      (node (ref "C7") (pin "2") (pinfunction "2_2") (pintype "passive"))
      (node (ref "C8") (pin "2") (pinfunction "2_2") (pintype "passive"))
      (node (ref "IC1") (pin "2") (pinfunction "DCDC_HGND_2") (pintype "passive"))
      (node (ref "IC1") (pin "7") (pinfunction "INN_7") (pintype "input"))
      (node (ref "IC1") (pin "8") (pinfunction "HGND_8") (pintype "passive"))
      (node (ref "R6") (pin "1") (pinfunction "1_1") (pintype "passive"))
      (node (ref "R7") (pin "1") (pinfunction "1_1") (pintype "passive"))
      (node (ref "X1") (pin "2") (pinfunction "1_2") (pintype "passive"))
    )
    (net (code "15") (name "AIN1P") (class "Default")
      (node (ref "L1") (pin "P$2") (pinfunction "2_P$2") (pintype "passive"))
      (node (ref "X1") (pin "1") (pinfunction "1_1") (pintype "passive"))
    )
    (net (code "16") (name "AIN3P") (class "Default")
      (node (ref "JP4") (pin "2") (pinfunction "2_2") (pintype "passive"))
      (node (ref "L3") (pin "P$1") (pinfunction "1_P$1") (pintype "passive"))
      (node (ref "OK2") (pin "4") (pinfunction "S1_4") (pintype "passive"))
      (node (ref "R17") (pin "2") (pinfunction "2_2") (pintype "passive"))
      (node (ref "R20") (pin "2") (pinfunction "2_2") (pintype "passive"))
    )
    (net (code "17") (name "AIN4N") (class "Default")
      (node (ref "D4") (pin "2") (pinfunction "A_2") (pintype "passive"))
      (node (ref "D5") (pin "1") (pinfunction "C_1") (pintype "passive"))
      (node (ref "D8") (pin "2") (pinfunction "A_2") (pintype "passive"))
      (node (ref "D9") (pin "1") (pinfunction "C_1") (pintype "passive"))
      (node (ref "JP6") (pin "1") (pinfunction "1_1") (pintype "passive"))
      (node (ref "R31") (pin "2") (pinfunction "2_2") (pintype "passive"))
      (node (ref "R35") (pin "1") (pinfunction "1_1") (pintype "passive"))
      (node (ref "TVS1") (pin "C1") (pinfunction "1_C1") (pintype "passive"))
      (node (ref "X1") (pin "8") (pinfunction "1_8") (pintype "passive"))
    )
    (net (code "18") (name "AIN4P") (class "Default")
      (node (ref "F4") (pin "2") (pinfunction "2_2") (pintype "passive"))
      (node (ref "X1") (pin "7") (pinfunction "1_7") (pintype "passive"))
    )
    (net (code "19") (name "AIN_U4") (class "Default")
      (node (ref "ISEL1A_1") (pin "10") (pinfunction "NC_10") (pintype "passive"))
      (node (ref "ISEL1A_1") (pin "3") (pinfunction "NC_3") (pintype "passive"))
      (node (ref "JP2") (pin "2") (pinfunction "2_2") (pintype "passive"))
      (node (ref "R36") (pin "2") (pinfunction "2_2") (pintype "passive"))
      (node (ref "R37") (pin "2") (pinfunction "2_2") (pintype "passive"))
      (node (ref "TVS1") (pin "C2") (pinfunction "2_C2") (pintype "passive"))
    )
    (net (code "20") (name "AVSS") (class "Default")
      (node (ref "C23") (pin "1") (pinfunction "1_1") (pintype "passive"))
      (node (ref "C25") (pin "1") (pinfunction "1_1") (pintype "passive"))
      (node (ref "C26") (pin "2") (pinfunction "2_2") (pintype "passive"))
      (node (ref "C27") (pin "1") (pinfunction "1_1") (pintype "passive"))
      (node (ref "C28") (pin "2") (pinfunction "2_2") (pintype "passive"))
      (node (ref "C33") (pin "1") (pinfunction "1_1") (pintype "passive"))
      (node (ref "C34") (pin "2") (pinfunction "2_2") (pintype "passive"))
      (node (ref "C54") (pin "1") (pinfunction "1_1") (pintype "passive"))
      (node (ref "C55") (pin "2") (pinfunction "2_2") (pintype "passive"))
      (node (ref "C58") (pin "2") (pinfunction "2_2") (pintype "passive"))
      (node (ref "C59") (pin "1") (pinfunction "1_1") (pintype "passive"))
      (node (ref "C63") (pin "1") (pinfunction "1_1") (pintype "passive"))
      (node (ref "C64") (pin "1") (pinfunction "1_1") (pintype "passive"))
      (node (ref "IC11") (pin "20") (pinfunction "AVSS_2_20") (pintype "power_in"))
      (node (ref "IC11") (pin "23") (pinfunction "AVSS_3_23") (pintype "power_in"))
      (node (ref "IC11") (pin "25") (pinfunction "VREFN_25") (pintype "input"))
      (node (ref "IC11") (pin "32") (pinfunction "AVSS_4_32") (pintype "power_in"))
      (node (ref "IC11") (pin "53") (pinfunction "AVSS1_53") (pintype "power_in"))
      (node (ref "IC11") (pin "57") (pinfunction "AVSS_5_57") (pintype "power_in"))
      (node (ref "IC11") (pin "58") (pinfunction "AVSS_58") (pintype "power_in"))
      (node (ref "IC8") (pin "3") (pinfunction "GND_3") (pintype "power_in"))
      (node (ref "IC8") (pin "4") (pinfunction "GND_4") (pintype "power_in"))
      (node (ref "IC8") (pin "5") (pinfunction "GND_5") (pintype "power_in"))
      (node (ref "IC8") (pin "8") (pinfunction "GND_8") (pintype "power_in"))
      (node (ref "R54") (pin "1") (pinfunction "1_1") (pintype "passive"))
      (node (ref "R65") (pin "2") (pinfunction "2_2") (pintype "passive"))
    )
    (net (code "21") (name "CURR_IN#3") (class "Default")
      (node (ref "OK2") (pin "3") (pinfunction "S2_3") (pintype "passive"))
      (node (ref "Q1") (pin "2") (pinfunction "D_2") (pintype "passive"))
      (node (ref "Q1") (pin "4") (pinfunction "D_4") (pintype "passive"))
    )
    (net (code "22") (name "DIAG#1") (class "Default")
      (node (ref "IC1") (pin "14") (pinfunction "DIAG_14") (pintype "output"))
      (node (ref "R4") (pin "1") (pinfunction "1_1") (pintype "passive"))
      (node (ref "X3") (pin "3") (pinfunction "1_3") (pintype "passive"))
    )
    (net (code "23") (name "DIAG#2") (class "Default")
      (node (ref "IC3") (pin "14") (pinfunction "DIAG_14") (pintype "output"))
      (node (ref "R9") (pin "1") (pinfunction "1_1") (pintype "passive"))
      (node (ref "X3") (pin "4") (pinfunction "1_4") (pintype "passive"))
    )
    (net (code "24") (name "GND") (class "Default")
      (node (ref "C11") (pin "2") (pinfunction "2_2") (pintype "passive"))
      (node (ref "C13") (pin "2") (pinfunction "2_2") (pintype "passive"))
      (node (ref "C14") (pin "2") (pinfunction "2_2") (pintype "passive"))
      (node (ref "C18") (pin "1") (pinfunction "1_1") (pintype "passive"))
      (node (ref "C19") (pin "1") (pinfunction "1_1") (pintype "passive"))
      (node (ref "C20") (pin "2") (pinfunction "2_2") (pintype "passive"))
      (node (ref "C21") (pin "1") (pinfunction "1_1") (pintype "passive"))
      (node (ref "C22") (pin "1") (pinfunction "1_1") (pintype "passive"))
      (node (ref "C3") (pin "2") (pinfunction "2_2") (pintype "passive"))
      (node (ref "C46") (pin "2") (pinfunction "2_2") (pintype "passive"))
      (node (ref "C47") (pin "2") (pinfunction "2_2") (pintype "passive"))
      (node (ref "C48") (pin "1") (pinfunction "1_1") (pintype "passive"))
      (node (ref "C49") (pin "1") (pinfunction "1_1") (pintype "passive"))
      (node (ref "C5") (pin "2") (pinfunction "2_2") (pintype "passive"))
      (node (ref "C56") (pin "2") (pinfunction "2_2") (pintype "passive"))
      (node (ref "C57") (pin "2") (pinfunction "2_2") (pintype "passive"))
      (node (ref "C6") (pin "2") (pinfunction "2_2") (pintype "passive"))
      (node (ref "C60") (pin "2") (pinfunction "2_2") (pintype "passive"))
      (node (ref "C61") (pin "1") (pinfunction "1_1") (pintype "passive"))
      (node (ref "C62") (pin "1") (pinfunction "1_1") (pintype "passive"))
      (node (ref "C63") (pin "2") (pinfunction "2_2") (pintype "passive"))
      (node (ref "C64") (pin "2") (pinfunction "2_2") (pintype "passive"))
      (node (ref "D2") (pin "1") (pinfunction "C_1") (pintype "passive"))
      (node (ref "D3") (pin "2") (pinfunction "A_2") (pintype "passive"))
      (node (ref "D4") (pin "1") (pinfunction "C_1") (pintype "passive"))
      (node (ref "D5") (pin "2") (pinfunction "A_2") (pintype "passive"))
      (node (ref "GND") (pin "1") (pinfunction "P$1_1") (pintype "bidirectional"))
      (node (ref "IC1") (pin "15") (pinfunction "DCDC_GND_15") (pintype "passive"))
      (node (ref "IC1") (pin "9") (pinfunction "GND_9") (pintype "passive"))
      (node (ref "IC11") (pin "31") (pinfunction "RESV1_31") (pintype "input"))
      (node (ref "IC11") (pin "33") (pinfunction "DGND_2_33") (pintype "power_in"))
      (node (ref "IC11") (pin "41") (pinfunction "DAISY_IN_41") (pintype "input"))
      (node (ref "IC11") (pin "49") (pinfunction "DGND_3_49") (pintype "power_in"))
      (node (ref "IC11") (pin "51") (pinfunction "DGND_51") (pintype "power_in"))
      (node (ref "IC12") (pin "2") (pinfunction "GND_2") (pintype "passive"))
      (node (ref "IC13") (pin "1") (pinfunction "GND_1") (pintype "passive"))
      (node (ref "IC2") (pin "9") (pinfunction "GND_9") (pintype "input"))
      (node (ref "IC3") (pin "15") (pinfunction "DCDC_GND_15") (pintype "passive"))
      (node (ref "IC3") (pin "9") (pinfunction "GND_9") (pintype "passive"))
      (node (ref "IC5") (pin "5") (pinfunction "GND_5") (pintype "power_in"))
      (node (ref "IC7") (pin "5") (pinfunction "GND_5") (pintype "power_in"))
      (node (ref "JP5") (pin "2") (pinfunction "2_2") (pintype "passive"))
      (node (ref "JP6") (pin "2") (pinfunction "2_2") (pintype "passive"))
      (node (ref "JP8") (pin "NO") (pinfunction "NO_NO") (pintype "passive"))
      (node (ref "OK1") (pin "2") (pinfunction "C_2") (pintype "passive"))
      (node (ref "OK2") (pin "2") (pinfunction "C_2") (pintype "passive"))
      (node (ref "OK3") (pin "2") (pinfunction "C_2") (pintype "passive"))
      (node (ref "R19") (pin "1") (pinfunction "1_1") (pintype "passive"))
      (node (ref "R27") (pin "2") (pinfunction "2_2") (pintype "passive"))
      (node (ref "R28") (pin "1") (pinfunction "1_1") (pintype "passive"))
      (node (ref "R31") (pin "1") (pinfunction "1_1") (pintype "passive"))
      (node (ref "X2") (pin "1") (pinfunction "1_1") (pintype "passive"))
      (node (ref "X2") (pin "11") (pinfunction "1_11") (pintype "passive"))
      (node (ref "X2") (pin "12") (pinfunction "1_12") (pintype "passive"))
      (node (ref "X2") (pin "2") (pinfunction "1_2") (pintype "passive"))
      (node (ref "X2") (pin "21") (pinfunction "1_21") (pintype "passive"))
      (node (ref "X2") (pin "22") (pinfunction "1_22") (pintype "passive"))
      (node (ref "X2") (pin "27") (pinfunction "1_27") (pintype "passive"))
      (node (ref "X2") (pin "28") (pinfunction "1_28") (pintype "passive"))
      (node (ref "X3") (pin "1") (pinfunction "1_1") (pintype "passive"))
      (node (ref "X3") (pin "27") (pinfunction "1_27") (pintype "passive"))
      (node (ref "X3") (pin "28") (pinfunction "1_28") (pintype "passive"))
    )
    (net (code "25") (name "HI_CLAMP") (class "Default")
      (node (ref "IC4") (pin "10") (pinfunction "+IN_10") (pintype "input"))
      (node (ref "IC4") (pin "5") (pinfunction "+IN_5") (pintype "input"))
      (node (ref "R26") (pin "2") (pinfunction "2_2") (pintype "passive"))
      (node (ref "R27") (pin "1") (pinfunction "1_1") (pintype "passive"))
    )
    (net (code "26") (name "IN1N") (class "Default")
      (node (ref "IC1") (pin "10") (pinfunction "OUTN_10") (pintype "output"))
      (node (ref "IC11") (pin "15") (pinfunction "IN1N_15") (pintype "input"))
    )
    (net (code "27") (name "IN1P") (class "Default")
      (node (ref "IC1") (pin "11") (pinfunction "OUTP_11") (pintype "output"))
      (node (ref "IC11") (pin "16") (pinfunction "IN1P_16") (pintype "input"))
    )
    (net (code "28") (name "IN2N") (class "Default")
      (node (ref "IC11") (pin "13") (pinfunction "IN2N_13") (pintype "input"))
      (node (ref "IC3") (pin "10") (pinfunction "OUTN_10") (pintype "output"))
    )
    (net (code "29") (name "IN2P") (class "Default")
      (node (ref "IC11") (pin "14") (pinfunction "IN2P_14") (pintype "input"))
      (node (ref "IC3") (pin "11") (pinfunction "OUTP_11") (pintype "output"))
    )
    (net (code "30") (name "IN3N") (class "Default")
      (node (ref "D2") (pin "2") (pinfunction "A_2") (pintype "passive"))
      (node (ref "D3") (pin "1") (pinfunction "C_1") (pintype "passive"))
      (node (ref "IC11") (pin "11") (pinfunction "IN3N_11") (pintype "input"))
      (node (ref "JP3") (pin "1") (pinfunction "1_1") (pintype "passive"))
      (node (ref "JP5") (pin "1") (pinfunction "1_1") (pintype "passive"))
      (node (ref "R15") (pin "1") (pinfunction "1_1") (pintype "passive"))
      (node (ref "R19") (pin "2") (pinfunction "2_2") (pintype "passive"))
      (node (ref "R25") (pin "1") (pinfunction "1_1") (pintype "passive"))
      (node (ref "X1") (pin "6") (pinfunction "1_6") (pintype "passive"))
    )
    (net (code "31") (name "IN3P") (class "Default")
      (node (ref "D1") (pin "3") (pinfunction "AC_3") (pintype "passive"))
      (node (ref "IC11") (pin "12") (pinfunction "IN3P_12") (pintype "input"))
      (node (ref "IC4") (pin "2") (pinfunction "-IN_2") (pintype "input"))
      (node (ref "IC4") (pin "6") (pinfunction "-IN_6") (pintype "input"))
      (node (ref "IC5") (pin "10") (pinfunction "D_10") (pintype "bidirectional"))
      (node (ref "IC5") (pin "15") (pinfunction "D_15") (pintype "bidirectional"))
      (node (ref "IC5") (pin "2") (pinfunction "D_2") (pintype "bidirectional"))
      (node (ref "IC5") (pin "7") (pinfunction "D_7") (pintype "bidirectional"))
    )
    (net (code "32") (name "IN4N") (class "Default")
      (node (ref "IC11") (pin "9") (pinfunction "IN4N_9") (pintype "input"))
      (node (ref "JP1") (pin "1") (pinfunction "1_1") (pintype "passive"))
      (node (ref "R35") (pin "1S") (pinfunction "1S_1S") (pintype "passive"))
      (node (ref "R39") (pin "1") (pinfunction "1_1") (pintype "passive"))
    )
    (net (code "33") (name "IN4P") (class "Default")
      (node (ref "D10") (pin "3") (pinfunction "AC_3") (pintype "passive"))
      (node (ref "IC11") (pin "10") (pinfunction "IN4P_10") (pintype "input"))
      (node (ref "IC4") (pin "13") (pinfunction "-IN_13") (pintype "input"))
      (node (ref "IC4") (pin "9") (pinfunction "-IN_9") (pintype "input"))
      (node (ref "IC7") (pin "11") (pinfunction "S_11") (pintype "bidirectional"))
      (node (ref "IC7") (pin "15") (pinfunction "D_15") (pintype "bidirectional"))
      (node (ref "IC7") (pin "3") (pinfunction "S_3") (pintype "bidirectional"))
      (node (ref "IC7") (pin "7") (pinfunction "D_7") (pintype "bidirectional"))
    )
    (net (code "34") (name "ISEL#3") (class "Default")
      (node (ref "IC5") (pin "9") (pinfunction "IN_9") (pintype "input"))
      (node (ref "R14") (pin "2") (pinfunction "2_2") (pintype "passive"))
    )
    (net (code "35") (name "ISEL10A_R4_OUT") (class "Default")
      (node (ref "IC2") (pin "11") (pinfunction "8C_11") (pintype "output"))
      (node (ref "ISEL10A_2") (pin "A1") (pinfunction "R_A1") (pintype "passive"))
    )
    (net (code "36") (name "ISEL10A_S4_OUT") (class "Default")
      (node (ref "IC2") (pin "12") (pinfunction "7C_12") (pintype "output"))
      (node (ref "ISEL10A_2") (pin "A2") (pinfunction "S_A2") (pintype "passive"))
    )
    (net (code "37") (name "ISEL10_R#4") (class "Default")
      (node (ref "IC2") (pin "8") (pinfunction "8B_8") (pintype "input"))
      (node (ref "X3") (pin "22") (pinfunction "1_22") (pintype "passive"))
    )
    (net (code "38") (name "ISEL10_S#4") (class "Default")
      (node (ref "IC2") (pin "7") (pinfunction "7B_7") (pintype "input"))
      (node (ref "X3") (pin "20") (pinfunction "1_20") (pintype "passive"))
    )
    (net (code "39") (name "ISEL_LOW#4") (class "Default")
      (node (ref "IC7") (pin "16") (pinfunction "IN_16") (pintype "input"))
      (node (ref "X3") (pin "23") (pinfunction "1_23") (pintype "passive"))
    )
    (net (code "40") (name "ISEL_MID#4") (class "Default")
      (node (ref "IC7") (pin "9") (pinfunction "IN_9") (pintype "input"))
      (node (ref "Q3") (pin "1") (pinfunction "G_1") (pintype "passive"))
      (node (ref "Q4") (pin "1") (pinfunction "G_1") (pintype "passive"))
      (node (ref "X3") (pin "24") (pinfunction "1_24") (pintype "passive"))
    )
    (net (code "41") (name "ISEL_R#2") (class "Default")
      (node (ref "IC2") (pin "4") (pinfunction "4B_4") (pintype "input"))
      (node (ref "X3") (pin "8") (pinfunction "1_8") (pintype "passive"))
    )
    (net (code "42") (name "ISEL_R#4") (class "Default")
      (node (ref "IC2") (pin "6") (pinfunction "6B_6") (pintype "input"))
      (node (ref "X3") (pin "18") (pinfunction "1_18") (pintype "passive"))
    )
    (net (code "43") (name "ISEL_R2_OUT") (class "Default")
      (node (ref "IC2") (pin "15") (pinfunction "4C_15") (pintype "output"))
      (node (ref "ISEL10A_1") (pin "A1") (pinfunction "R_A1") (pintype "passive"))
    )
    (net (code "44") (name "ISEL_R4_OUT") (class "Default")
      (node (ref "IC2") (pin "13") (pinfunction "6C_13") (pintype "output"))
      (node (ref "ISEL1A_1") (pin "7") (pinfunction "R-_7") (pintype "passive"))
    )
    (net (code "45") (name "ISEL_S#2") (class "Default")
      (node (ref "IC2") (pin "3") (pinfunction "3B_3") (pintype "input"))
      (node (ref "X3") (pin "6") (pinfunction "1_6") (pintype "passive"))
    )
    (net (code "46") (name "ISEL_S#4") (class "Default")
      (node (ref "IC2") (pin "5") (pinfunction "5B_5") (pintype "input"))
      (node (ref "X3") (pin "16") (pinfunction "1_16") (pintype "passive"))
    )
    (net (code "47") (name "ISEL_S2_OUT") (class "Default")
      (node (ref "IC2") (pin "16") (pinfunction "3C_16") (pintype "output"))
      (node (ref "ISEL10A_1") (pin "A2") (pinfunction "S_A2") (pintype "passive"))
    )
    (net (code "48") (name "ISEL_S4_OUT") (class "Default")
      (node (ref "IC2") (pin "14") (pinfunction "5C_14") (pintype "output"))
      (node (ref "ISEL1A_1") (pin "12") (pinfunction "S-_12") (pintype "passive"))
    )
    (net (code "49") (name "LO_CLAMP") (class "Default")
      (node (ref "IC4") (pin "12") (pinfunction "+IN_12") (pintype "input"))
      (node (ref "IC4") (pin "3") (pinfunction "+IN_3") (pintype "input"))
      (node (ref "R28") (pin "2") (pinfunction "2_2") (pintype "passive"))
      (node (ref "R29") (pin "1") (pinfunction "1_1") (pintype "passive"))
    )
    (net (code "50") (name "Net-(C35-Pad2)") (class "Default")
      (node (ref "C35") (pin "2") (pinfunction "2_2") (pintype "passive"))
      (node (ref "R65") (pin "1") (pinfunction "1_1") (pintype "passive"))
    )
    (net (code "51") (name "Net-(D1-A)") (class "Default")
      (node (ref "D1") (pin "1") (pinfunction "A_1") (pintype "passive"))
      (node (ref "IC4") (pin "1") (pinfunction "OUT_1") (pintype "output"))
    )
    (net (code "52") (name "Net-(D1-C)") (class "Default")
      (node (ref "D1") (pin "2") (pinfunction "C_2") (pintype "passive"))
      (node (ref "IC4") (pin "7") (pinfunction "OUT_7") (pintype "output"))
    )
    (net (code "53") (name "Net-(D6-A)") (class "Default")
      (node (ref "D6") (pin "2") (pinfunction "A_2") (pintype "passive"))
      (node (ref "D7") (pin "1") (pinfunction "C_1") (pintype "passive"))
      (node (ref "IC7") (pin "14") (pinfunction "S_14") (pintype "bidirectional"))
      (node (ref "ISEL1A_1") (pin "5") (pinfunction "NO_5") (pintype "passive"))
      (node (ref "ISEL1A_1") (pin "8") (pinfunction "NO_8") (pintype "passive"))
      (node (ref "Q3") (pin "2") (pinfunction "S_2") (pintype "passive"))
      (node (ref "R30") (pin "2") (pinfunction "2_2") (pintype "passive"))
      (node (ref "R33") (pin "2") (pinfunction "2_2") (pintype "passive"))
    )
    (net (code "54") (name "Net-(D6-C)") (class "Default")
      (node (ref "D6") (pin "1") (pinfunction "C_1") (pintype "passive"))
      (node (ref "D7") (pin "2") (pinfunction "A_2") (pintype "passive"))
      (node (ref "D8") (pin "1") (pinfunction "C_1") (pintype "passive"))
      (node (ref "D9") (pin "2") (pinfunction "A_2") (pintype "passive"))
      (node (ref "R34") (pin "2") (pinfunction "2_2") (pintype "passive"))
    )
    (net (code "55") (name "Net-(D10-A)") (class "Default")
      (node (ref "D10") (pin "1") (pinfunction "A_1") (pintype "passive"))
      (node (ref "IC4") (pin "14") (pinfunction "OUT_14") (pintype "output"))
    )
    (net (code "56") (name "Net-(D10-C)") (class "Default")
      (node (ref "D10") (pin "2") (pinfunction "C_2") (pintype "passive"))
      (node (ref "IC4") (pin "8") (pinfunction "OUT_8") (pintype "output"))
    )
    (net (code "57") (name "Net-(F3-P$1)") (class "Default")
      (node (ref "F3") (pin "1") (pinfunction "P$1_1") (pintype "bidirectional"))
      (node (ref "R13") (pin "1") (pinfunction "1_1") (pintype "passive"))
    )
    (net (code "58") (name "Net-(F3-P$2)") (class "Default")
      (node (ref "F3") (pin "2") (pinfunction "P$2_2") (pintype "bidirectional"))
      (node (ref "Q1") (pin "1") (pinfunction "G_1") (pintype "passive"))
      (node (ref "Q2") (pin "3") (pinfunction "S_3") (pintype "passive"))
    )
    (net (code "59") (name "Net-(IC1-DCDC_IN)") (class "Default")
      (node (ref "C3") (pin "1") (pinfunction "1_1") (pintype "passive"))
      (node (ref "IC1") (pin "13") (pinfunction "LDO_OUT_13") (pintype "passive"))
      (node (ref "IC1") (pin "16") (pinfunction "DCDC_IN_16") (pintype "passive"))
    )
    (net (code "60") (name "Net-(IC1-DCDC_OUT)") (class "Default")
      (node (ref "C1") (pin "1") (pinfunction "1_1") (pintype "passive"))
      (node (ref "C2") (pin "1") (pinfunction "1_1") (pintype "passive"))
      (node (ref "C4") (pin "2") (pinfunction "2_2") (pintype "passive"))
      (node (ref "IC1") (pin "1") (pinfunction "DCDC_OUT_1") (pintype "passive"))
      (node (ref "IC1") (pin "3") (pinfunction "HLDO_IN_3") (pintype "passive"))
    )
    (net (code "61") (name "Net-(IC1-HLDO_OUT)") (class "Default")
      (node (ref "C7") (pin "1") (pinfunction "1_1") (pintype "passive"))
      (node (ref "C8") (pin "1") (pinfunction "1_1") (pintype "passive"))
      (node (ref "IC1") (pin "5") (pinfunction "HLDO_OUT_5") (pintype "passive"))
    )
    (net (code "62") (name "Net-(IC1-INP)") (class "Default")
      (node (ref "IC1") (pin "6") (pinfunction "INP_6") (pintype "input"))
      (node (ref "OK1") (pin "4") (pinfunction "S1_4") (pintype "passive"))
      (node (ref "R5") (pin "1") (pinfunction "1_1") (pintype "passive"))
      (node (ref "R7") (pin "2") (pinfunction "2_2") (pintype "passive"))
    )
    (net (code "63") (name "Net-(IC2-COM)") (class "Default")
      (node (ref "IC2") (pin "10") (pinfunction "COM_10") (pintype "passive"))
      (node (ref "ZD1") (pin "C") (pinfunction "C_C") (pintype "passive"))
    )
    (net (code "64") (name "Net-(IC3-DCDC_HGND)") (class "Default")
      (node (ref "C10") (pin "2") (pinfunction "2_2") (pintype "passive"))
      (node (ref "C12") (pin "1") (pinfunction "1_1") (pintype "passive"))
      (node (ref "C15") (pin "2") (pinfunction "2_2") (pintype "passive"))
      (node (ref "C16") (pin "2") (pinfunction "2_2") (pintype "passive"))
      (node (ref "C9") (pin "2") (pinfunction "2_2") (pintype "passive"))
      (node (ref "IC3") (pin "2") (pinfunction "DCDC_HGND_2") (pintype "passive"))
      (node (ref "IC3") (pin "8") (pinfunction "HGND_8") (pintype "passive"))
      (node (ref "L2") (pin "2") (pinfunction "2_2") (pintype "passive"))
      (node (ref "R12") (pin "2") (pinfunction "2_2") (pintype "passive"))
    )
    (net (code "65") (name "Net-(IC3-DCDC_IN)") (class "Default")
      (node (ref "C11") (pin "1") (pinfunction "1_1") (pintype "passive"))
      (node (ref "IC3") (pin "13") (pinfunction "LDO_OUT_13") (pintype "passive"))
      (node (ref "IC3") (pin "16") (pinfunction "DCDC_IN_16") (pintype "passive"))
    )
    (net (code "66") (name "Net-(IC3-DCDC_OUT)") (class "Default")
      (node (ref "C10") (pin "1") (pinfunction "1_1") (pintype "passive"))
      (node (ref "C12") (pin "2") (pinfunction "2_2") (pintype "passive"))
      (node (ref "C9") (pin "1") (pinfunction "1_1") (pintype "passive"))
      (node (ref "IC3") (pin "1") (pinfunction "DCDC_OUT_1") (pintype "passive"))
      (node (ref "IC3") (pin "3") (pinfunction "HLDO_IN_3") (pintype "passive"))
    )
    (net (code "67") (name "Net-(IC3-HLDO_OUT)") (class "Default")
      (node (ref "C15") (pin "1") (pinfunction "1_1") (pintype "passive"))
      (node (ref "C16") (pin "1") (pinfunction "1_1") (pintype "passive"))
      (node (ref "IC3") (pin "5") (pinfunction "HLDO_OUT_5") (pintype "passive"))
    )
    (net (code "68") (name "Net-(IC3-INN)") (class "Default")
      (node (ref "C17") (pin "2") (pinfunction "2_2") (pintype "passive"))
      (node (ref "IC3") (pin "7") (pinfunction "INN_7") (pintype "input"))
      (node (ref "R12") (pin "1") (pinfunction "1_1") (pintype "passive"))
    )
    (net (code "69") (name "Net-(IC3-INP)") (class "Default")
      (node (ref "C17") (pin "1") (pinfunction "1_1") (pintype "passive"))
      (node (ref "IC3") (pin "6") (pinfunction "INP_6") (pintype "input"))
      (node (ref "R10") (pin "1") (pinfunction "1_1") (pintype "passive"))
    )
    (net (code "70") (name "Net-(IC5A-S)") (class "Default")
      (node (ref "IC5") (pin "3") (pinfunction "S_3") (pintype "bidirectional"))
      (node (ref "R22") (pin "1") (pinfunction "1_1") (pintype "passive"))
      (node (ref "R23") (pin "2") (pinfunction "2_2") (pintype "passive"))
    )
    (net (code "71") (name "Net-(IC5B-S)") (class "Default")
      (node (ref "IC5") (pin "14") (pinfunction "S_14") (pintype "bidirectional"))
      (node (ref "R24") (pin "1") (pinfunction "1_1") (pintype "passive"))
      (node (ref "R25") (pin "2") (pinfunction "2_2") (pintype "passive"))
    )
    (net (code "72") (name "Net-(IC5C-S)") (class "Default")
      (node (ref "IC5") (pin "11") (pinfunction "S_11") (pintype "bidirectional"))
      (node (ref "Q2") (pin "2") (pinfunction "D_2") (pintype "passive"))
      (node (ref "Q2") (pin "4") (pinfunction "D_4") (pintype "passive"))
      (node (ref "R15") (pin "2") (pinfunction "2_2") (pintype "passive"))
    )
    (net (code "73") (name "Net-(IC5D-S)") (class "Default")
      (node (ref "IC5") (pin "6") (pinfunction "S_6") (pintype "bidirectional"))
      (node (ref "OK3") (pin "4") (pinfunction "S1_4") (pintype "passive"))
    )
    (net (code "74") (name "Net-(IC6A-+IN)") (class "Default")
      (node (ref "IC6") (pin "3") (pinfunction "+IN_3") (pintype "input"))
      (node (ref "R33") (pin "1") (pinfunction "1_1") (pintype "passive"))
    )
    (net (code "75") (name "Net-(IC6A--IN)") (class "Default")
      (node (ref "IC6") (pin "1") (pinfunction "OUT_1") (pintype "output"))
      (node (ref "IC6") (pin "4") (pinfunction "-IN_4") (pintype "input"))
      (node (ref "R34") (pin "1") (pinfunction "1_1") (pintype "passive"))
    )
    (net (code "76") (name "Net-(IC7A-D)") (class "Default")
      (node (ref "IC7") (pin "2") (pinfunction "D_2") (pintype "bidirectional"))
      (node (ref "R38") (pin "1") (pinfunction "1_1") (pintype "passive"))
      (node (ref "R39") (pin "2") (pinfunction "2_2") (pintype "passive"))
    )
    (net (code "77") (name "Net-(IC7C-D)") (class "Default")
      (node (ref "IC7") (pin "10") (pinfunction "D_10") (pintype "bidirectional"))
      (node (ref "Q4") (pin "2") (pinfunction "S_2") (pintype "passive"))
      (node (ref "R30") (pin "1") (pinfunction "1_1") (pintype "passive"))
      (node (ref "R32") (pin "2") (pinfunction "2_2") (pintype "passive"))
    )
    (net (code "78") (name "Net-(IC7D-S)") (class "Default")
      (node (ref "IC7") (pin "6") (pinfunction "S_6") (pintype "bidirectional"))
      (node (ref "R36") (pin "1") (pinfunction "1_1") (pintype "passive"))
    )
    (net (code "79") (name "Net-(IC11-AVDD)") (class "Default")
      (node (ref "C54") (pin "2") (pinfunction "2_2") (pintype "passive"))
      (node (ref "C55") (pin "1") (pinfunction "1_1") (pintype "passive"))
      (node (ref "C56") (pin "1") (pinfunction "1_1") (pintype "passive"))
      (node (ref "C57") (pin "1") (pinfunction "1_1") (pintype "passive"))
      (node (ref "C58") (pin "1") (pinfunction "1_1") (pintype "passive"))
      (node (ref "C59") (pin "2") (pinfunction "2_2") (pintype "passive"))
      (node (ref "IC11") (pin "19") (pinfunction "AVDD_2_19") (pintype "power_in"))
      (node (ref "IC11") (pin "21") (pinfunction "AVDD_3_21") (pintype "power_in"))
      (node (ref "IC11") (pin "22") (pinfunction "AVDD_4_22") (pintype "power_in"))
      (node (ref "IC11") (pin "54") (pinfunction "AVDD1_54") (pintype "power_in"))
      (node (ref "IC11") (pin "56") (pinfunction "AVDD_5_56") (pintype "power_in"))
      (node (ref "IC11") (pin "59") (pinfunction "AVDD_59") (pintype "power_in"))
      (node (ref "R53") (pin "2") (pinfunction "2_2") (pintype "passive"))
    )
    (net (code "80") (name "Net-(IC11-CLK)") (class "Default")
      (node (ref "IC11") (pin "37") (pinfunction "CLK_37") (pintype "input"))
      (node (ref "JP9") (pin "2") (pinfunction "2_2") (pintype "passive"))
    )
    (net (code "81") (name "Net-(IC11-CLKSEL)") (class "Default")
      (node (ref "IC11") (pin "52") (pinfunction "CLKSEL_52") (pintype "input"))
      (node (ref "R52") (pin "1") (pinfunction "1_1") (pintype "passive"))
    )
    (net (code "82") (name "Net-(IC11-VCAP1)") (class "Default")
      (node (ref "C33") (pin "2") (pinfunction "2_2") (pintype "passive"))
      (node (ref "IC11") (pin "28") (pinfunction "VCAP1_28") (pintype "passive"))
    )
    (net (code "83") (name "Net-(IC11-VCAP2)") (class "Default")
      (node (ref "C27") (pin "2") (pinfunction "2_2") (pintype "passive"))
      (node (ref "IC11") (pin "30") (pinfunction "VCAP2_30") (pintype "passive"))
    )
    (net (code "84") (name "Net-(IC11-VCAP3)") (class "Default")
      (node (ref "C25") (pin "2") (pinfunction "2_2") (pintype "passive"))
      (node (ref "C26") (pin "1") (pinfunction "1_1") (pintype "passive"))
      (node (ref "IC11") (pin "55") (pinfunction "VCAP3_55") (pintype "passive"))
    )
    (net (code "85") (name "Net-(IC11-VCAP4)") (class "Default")
      (node (ref "C23") (pin "2") (pinfunction "2_2") (pintype "passive"))
      (node (ref "IC11") (pin "26") (pinfunction "VCAP4_26") (pintype "output"))
    )
    (net (code "86") (name "Net-(IC11-VREFP)") (class "Default")
      (node (ref "C28") (pin "1") (pinfunction "1_1") (pintype "passive"))
      (node (ref "C34") (pin "1") (pinfunction "1_1") (pintype "passive"))
      (node (ref "C35") (pin "1") (pinfunction "1_1") (pintype "passive"))
      (node (ref "IC11") (pin "24") (pinfunction "VREFP_24") (pintype "bidirectional"))
      (node (ref "IC8") (pin "6") (pinfunction "VOUT_S_6") (pintype "output"))
      (node (ref "IC8") (pin "7") (pinfunction "VOUT_F_7") (pintype "output"))
    )
    (net (code "87") (name "Net-(IC11-~{PWDN})") (class "Default")
      (node (ref "IC11") (pin "35") (pinfunction "~{PWDN}_35") (pintype "input"))
      (node (ref "R51") (pin "1") (pinfunction "1_1") (pintype "passive"))
    )
    (net (code "88") (name "Net-(IC12-EN)") (class "Default")
      (node (ref "C46") (pin "1") (pinfunction "1_1") (pintype "passive"))
      (node (ref "IC12") (pin "1") (pinfunction "IN_1") (pintype "input"))
      (node (ref "IC12") (pin "3") (pinfunction "EN_3") (pintype "input"))
      (node (ref "L4") (pin "P$1") (pinfunction "1_P$1") (pintype "passive"))
    )
    (net (code "89") (name "Net-(IC13-EN)") (class "Default")
      (node (ref "C47") (pin "1") (pinfunction "1_1") (pintype "passive"))
      (node (ref "IC13") (pin "2") (pinfunction "IN_2") (pintype "input"))
      (node (ref "IC13") (pin "3") (pinfunction "EN_3") (pintype "input"))
      (node (ref "L5") (pin "P$1") (pinfunction "1_P$1") (pintype "passive"))
    )
    (net (code "90") (name "Net-(ISEL1A_1B-COM)") (class "Default")
      (node (ref "F5") (pin "1") (pinfunction "1_1") (pintype "passive"))
      (node (ref "ISEL1A_1") (pin "4") (pinfunction "COM_4") (pintype "passive"))
      (node (ref "ISEL1A_1") (pin "9") (pinfunction "COM_9") (pintype "passive"))
    )
    (net (code "91") (name "Net-(ISEL10A_1B-COM)") (class "Default")
      (node (ref "F1") (pin "1") (pinfunction "1_1") (pintype "passive"))
      (node (ref "F2") (pin "1") (pinfunction "1_1") (pintype "passive"))
      (node (ref "ISEL10A_1") (pin "11") (pinfunction "COM_11") (pintype "passive"))
    )
    (net (code "92") (name "Net-(ISEL10A_1B-NC)") (class "Default")
      (node (ref "ISEL10A_1") (pin "12") (pinfunction "NC_12") (pintype "passive"))
      (node (ref "R11") (pin "2") (pinfunction "2_2") (pintype "passive"))
      (node (ref "R8") (pin "1") (pinfunction "1_1") (pintype "passive"))
    )
    (net (code "93") (name "Net-(ISEL10A_1C-COM)") (class "Default")
      (node (ref "ISEL10A_1") (pin "21") (pinfunction "COM_21") (pintype "passive"))
      (node (ref "L2") (pin "4") (pinfunction "4_4") (pintype "passive"))
    )
    (net (code "94") (name "Net-(ISEL10A_1C-NC)") (class "Default")
      (node (ref "ISEL10A_1") (pin "22") (pinfunction "NC_22") (pintype "passive"))
      (node (ref "R11") (pin "2S") (pinfunction "2S_2S") (pintype "passive"))
    )
    (net (code "95") (name "Net-(ISEL10A_1C-NO)") (class "Default")
      (node (ref "F2") (pin "2") (pinfunction "2_2") (pintype "passive"))
      (node (ref "ISEL10A_1") (pin "24") (pinfunction "NO_24") (pintype "passive"))
      (node (ref "R8") (pin "2") (pinfunction "2_2") (pintype "passive"))
    )
    (net (code "96") (name "Net-(ISEL10A_2B-COM)") (class "Default")
      (node (ref "F4") (pin "1") (pinfunction "1_1") (pintype "passive"))
      (node (ref "ISEL10A_2") (pin "11") (pinfunction "COM_11") (pintype "passive"))
      (node (ref "ISEL10A_2") (pin "21") (pinfunction "COM_21") (pintype "passive"))
    )
    (net (code "97") (name "Net-(ISEL10A_2B-NC)") (class "Default")
      (node (ref "ISEL10A_2") (pin "12") (pinfunction "NC_12") (pintype "passive"))
      (node (ref "ISEL10A_2") (pin "22") (pinfunction "NC_22") (pintype "passive"))
      (node (ref "R32") (pin "1") (pinfunction "1_1") (pintype "passive"))
      (node (ref "R35") (pin "2") (pinfunction "2_2") (pintype "passive"))
      (node (ref "R35") (pin "2S") (pinfunction "2S_2S") (pintype "passive"))
    )
    (net (code "98") (name "Net-(ISEL10A_2B-NO)") (class "Default")
      (node (ref "F5") (pin "2") (pinfunction "2_2") (pintype "passive"))
      (node (ref "ISEL10A_2") (pin "14") (pinfunction "NO_14") (pintype "passive"))
      (node (ref "ISEL10A_2") (pin "24") (pinfunction "NO_24") (pintype "passive"))
    )
    (net (code "99") (name "Net-(JP8-PadCOM)") (class "Default")
      (node (ref "JP8") (pin "COM") (pinfunction "COM_COM") (pintype "passive"))
      (node (ref "R52") (pin "2") (pinfunction "2_2") (pintype "passive"))
    )
    (net (code "100") (name "Net-(L1-1)") (class "Default")
      (node (ref "L1") (pin "P$1") (pinfunction "1_P$1") (pintype "passive"))
      (node (ref "R1") (pin "2") (pinfunction "2_2") (pintype "passive"))
    )
    (net (code "101") (name "Net-(L2-Pad1)") (class "Default")
      (node (ref "L2") (pin "1") (pinfunction "1_1") (pintype "passive"))
      (node (ref "R11") (pin "1S") (pinfunction "1S_1S") (pintype "passive"))
    )
    (net (code "102") (name "Net-(L2-Pad3)") (class "Default")
      (node (ref "L2") (pin "3") (pinfunction "3_3") (pintype "passive"))
      (node (ref "R10") (pin "2") (pinfunction "2_2") (pintype "passive"))
    )
    (net (code "103") (name "Net-(L3-2)") (class "Default")
      (node (ref "L3") (pin "P$2") (pinfunction "2_P$2") (pintype "passive"))
      (node (ref "X1") (pin "5") (pinfunction "1_5") (pintype "passive"))
    )
    (net (code "104") (name "Net-(OK1-A)") (class "Default")
      (node (ref "OK1") (pin "1") (pinfunction "A_1") (pintype "passive"))
      (node (ref "R2") (pin "1") (pinfunction "1_1") (pintype "passive"))
    )
    (net (code "105") (name "Net-(OK1-S2)") (class "Default")
      (node (ref "OK1") (pin "3") (pinfunction "S2_3") (pintype "passive"))
      (node (ref "R6") (pin "2") (pinfunction "2_2") (pintype "passive"))
    )
    (net (code "106") (name "Net-(OK2-A)") (class "Default")
      (node (ref "OK2") (pin "1") (pinfunction "A_1") (pintype "passive"))
      (node (ref "R14") (pin "1") (pinfunction "1_1") (pintype "passive"))
    )
    (net (code "107") (name "Net-(OK3-A)") (class "Default")
      (node (ref "OK3") (pin "1") (pinfunction "A_1") (pintype "passive"))
      (node (ref "R16") (pin "2") (pinfunction "2_2") (pintype "passive"))
    )
    (net (code "108") (name "Net-(OK3-S2)") (class "Default")
      (node (ref "OK3") (pin "3") (pinfunction "S2_3") (pintype "passive"))
      (node (ref "R18") (pin "1") (pinfunction "1_1") (pintype "passive"))
    )
    (net (code "109") (name "Net-(Q1-S)") (class "Default")
      (node (ref "Q1") (pin "3") (pinfunction "S_3") (pintype "passive"))
      (node (ref "Q2") (pin "1") (pinfunction "G_1") (pintype "passive"))
      (node (ref "R13") (pin "2") (pinfunction "2_2") (pintype "passive"))
    )
    (net (code "110") (name "Net-(Q3-D)") (class "Default")
      (node (ref "Q3") (pin "3") (pinfunction "D_3") (pintype "passive"))
      (node (ref "Q4") (pin "3") (pinfunction "D_3") (pintype "passive"))
    )
    (net (code "111") (name "Net-(R1-Pad1)") (class "Default")
      (node (ref "R1") (pin "1") (pinfunction "1_1") (pintype "passive"))
      (node (ref "R3") (pin "2") (pinfunction "2_2") (pintype "passive"))
    )
    (net (code "112") (name "Net-(R3-Pad1)") (class "Default")
      (node (ref "R3") (pin "1") (pinfunction "1_1") (pintype "passive"))
      (node (ref "R5") (pin "2") (pinfunction "2_2") (pintype "passive"))
    )
    (net (code "113") (name "Net-(R17-Pad1)") (class "Default")
      (node (ref "R17") (pin "1") (pinfunction "1_1") (pintype "passive"))
      (node (ref "R18") (pin "2") (pinfunction "2_2") (pintype "passive"))
    )
    (net (code "114") (name "Net-(R20-Pad1)") (class "Default")
      (node (ref "R20") (pin "1") (pinfunction "1_1") (pintype "passive"))
      (node (ref "R21") (pin "2") (pinfunction "2_2") (pintype "passive"))
    )
    (net (code "115") (name "Net-(R21-Pad1)") (class "Default")
      (node (ref "R21") (pin "1") (pinfunction "1_1") (pintype "passive"))
      (node (ref "R22") (pin "2") (pinfunction "2_2") (pintype "passive"))
    )
    (net (code "116") (name "Net-(R23-Pad1)") (class "Default")
      (node (ref "R23") (pin "1") (pinfunction "1_1") (pintype "passive"))
      (node (ref "R24") (pin "2") (pinfunction "2_2") (pintype "passive"))
    )
    (net (code "117") (name "Net-(R37-Pad1)") (class "Default")
      (node (ref "R37") (pin "1") (pinfunction "1_1") (pintype "passive"))
      (node (ref "R38") (pin "2") (pinfunction "2_2") (pintype "passive"))
    )
    (net (code "118") (name "Net-(X1C-1)") (class "Default")
      (node (ref "F1") (pin "2") (pinfunction "2_2") (pintype "passive"))
      (node (ref "X1") (pin "3") (pinfunction "1_3") (pintype "passive"))
    )
    (net (code "119") (name "Net-(X1D-1)") (class "Default")
      (node (ref "R11") (pin "1") (pinfunction "1_1") (pintype "passive"))
      (node (ref "X1") (pin "4") (pinfunction "1_4") (pintype "passive"))
    )
    (net (code "120") (name "Net-(X2P-1)") (class "Default")
      (node (ref "JP1") (pin "2") (pinfunction "2_2") (pintype "passive"))
      (node (ref "X2") (pin "23") (pinfunction "1_23") (pintype "passive"))
    )
    (net (code "121") (name "Net-(X2Q-1)") (class "Default")
      (node (ref "JP2") (pin "1") (pinfunction "1_1") (pintype "passive"))
      (node (ref "X2") (pin "24") (pinfunction "1_24") (pintype "passive"))
    )
    (net (code "122") (name "Net-(X2R-1)") (class "Default")
      (node (ref "JP3") (pin "2") (pinfunction "2_2") (pintype "passive"))
      (node (ref "X2") (pin "25") (pinfunction "1_25") (pintype "passive"))
    )
    (net (code "123") (name "Net-(X2S-1)") (class "Default")
      (node (ref "JP4") (pin "1") (pinfunction "1_1") (pintype "passive"))
      (node (ref "X2") (pin "26") (pinfunction "1_26") (pintype "passive"))
    )
    (net (code "124") (name "USEL#1") (class "Default")
      (node (ref "R2") (pin "2") (pinfunction "2_2") (pintype "passive"))
      (node (ref "X3") (pin "5") (pinfunction "1_5") (pintype "passive"))
    )
    (net (code "125") (name "USEL1#3") (class "Default")
      (node (ref "IC5") (pin "8") (pinfunction "IN_8") (pintype "input"))
      (node (ref "R16") (pin "1") (pinfunction "1_1") (pintype "passive"))
      (node (ref "X3") (pin "11") (pinfunction "1_11") (pintype "passive"))
    )
    (net (code "126") (name "USEL1#4") (class "Default")
      (node (ref "IC7") (pin "8") (pinfunction "IN_8") (pintype "input"))
      (node (ref "X3") (pin "12") (pinfunction "1_12") (pintype "passive"))
    )
    (net (code "127") (name "USEL5#4") (class "Default")
      (node (ref "IC7") (pin "1") (pinfunction "IN_1") (pintype "input"))
      (node (ref "X3") (pin "14") (pinfunction "1_14") (pintype "passive"))
    )
    (net (code "128") (name "USEL20#3") (class "Default")
      (node (ref "IC5") (pin "1") (pinfunction "IN_1") (pintype "input"))
      (node (ref "X3") (pin "13") (pinfunction "1_13") (pintype "passive"))
    )
    (net (code "129") (name "USEL100#3") (class "Default")
      (node (ref "IC5") (pin "16") (pinfunction "IN_16") (pintype "input"))
      (node (ref "X3") (pin "9") (pinfunction "1_9") (pintype "passive"))
    )
    (net (code "130") (name "unconnected-(IC2-1B-Pad1)") (class "Default")
      (node (ref "IC2") (pin "1") (pinfunction "1B_1") (pintype "input"))
    )
    (net (code "131") (name "unconnected-(IC2-1C-Pad18)") (class "Default")
      (node (ref "IC2") (pin "18") (pinfunction "1C_18") (pintype "output"))
    )
    (net (code "132") (name "unconnected-(IC2-2B-Pad2)") (class "Default")
      (node (ref "IC2") (pin "2") (pinfunction "2B_2") (pintype "input"))
    )
    (net (code "133") (name "unconnected-(IC2-2C-Pad17)") (class "Default")
      (node (ref "IC2") (pin "17") (pinfunction "2C_17") (pintype "output"))
    )
    (net (code "134") (name "unconnected-(IC11-GPIO1-Pad42)") (class "Default")
      (node (ref "IC11") (pin "42") (pinfunction "GPIO1_42") (pintype "bidirectional"))
    )
    (net (code "135") (name "unconnected-(IC11-GPIO2-Pad44)") (class "Default")
      (node (ref "IC11") (pin "44") (pinfunction "GPIO2_44") (pintype "bidirectional"))
    )
    (net (code "136") (name "unconnected-(IC11-GPIO3-Pad45)") (class "Default")
      (node (ref "IC11") (pin "45") (pinfunction "GPIO3_45") (pintype "bidirectional"))
    )
    (net (code "137") (name "unconnected-(IC11-GPIO4-Pad46)") (class "Default")
      (node (ref "IC11") (pin "46") (pinfunction "GPIO4_46") (pintype "bidirectional"))
    )
    (net (code "138") (name "unconnected-(IC11-IN5N(NC)-Pad7)") (class "Default")
      (node (ref "IC11") (pin "7") (pinfunction "IN5N(NC)_7") (pintype "input"))
    )
    (net (code "139") (name "unconnected-(IC11-IN5P(NC)-Pad8)") (class "Default")
      (node (ref "IC11") (pin "8") (pinfunction "IN5P(NC)_8") (pintype "input"))
    )
    (net (code "140") (name "unconnected-(IC11-IN6N(NC)-Pad5)") (class "Default")
      (node (ref "IC11") (pin "5") (pinfunction "IN6N(NC)_5") (pintype "input"))
    )
    (net (code "141") (name "unconnected-(IC11-IN6P(NC)-Pad6)") (class "Default")
      (node (ref "IC11") (pin "6") (pinfunction "IN6P(NC)_6") (pintype "input"))
    )
    (net (code "142") (name "unconnected-(IC11-IN7N(NC)-Pad3)") (class "Default")
      (node (ref "IC11") (pin "3") (pinfunction "IN7N(NC)_3") (pintype "input"))
    )
    (net (code "143") (name "unconnected-(IC11-IN7P(NC)-Pad4)") (class "Default")
      (node (ref "IC11") (pin "4") (pinfunction "IN7P(NC)_4") (pintype "input"))
    )
    (net (code "144") (name "unconnected-(IC11-IN8N(NC)-Pad1)") (class "Default")
      (node (ref "IC11") (pin "1") (pinfunction "IN8N(NC)_1") (pintype "input"))
    )
    (net (code "145") (name "unconnected-(IC11-IN8P(NC)-Pad2)") (class "Default")
      (node (ref "IC11") (pin "2") (pinfunction "IN8P(NC)_2") (pintype "input"))
    )
    (net (code "146") (name "unconnected-(IC11-OPAMPN-Pad61)") (class "Default")
      (node (ref "IC11") (pin "61") (pinfunction "OPAMPN_61") (pintype "input"))
    )
    (net (code "147") (name "unconnected-(IC11-OPAMPOUT-Pad63)") (class "Default")
      (node (ref "IC11") (pin "63") (pinfunction "OPAMPOUT_63") (pintype "output"))
    )
    (net (code "148") (name "unconnected-(IC11-OPAMPP-Pad60)") (class "Default")
      (node (ref "IC11") (pin "60") (pinfunction "OPAMPP_60") (pintype "input"))
    )
    (net (code "149") (name "unconnected-(IC11-TESTN-Pad18)") (class "Default")
      (node (ref "IC11") (pin "18") (pinfunction "TESTN_18") (pintype "bidirectional"))
    )
    (net (code "150") (name "unconnected-(IC11-TESTP-Pad17)") (class "Default")
      (node (ref "IC11") (pin "17") (pinfunction "TESTP_17") (pintype "bidirectional"))
    )
    (net (code "151") (name "unconnected-(IC12-NR-Pad4)") (class "Default")
      (node (ref "IC12") (pin "4") (pinfunction "NR_4") (pintype "passive"))
    )
    (net (code "152") (name "unconnected-(IC13-NR-Pad4)") (class "Default")
      (node (ref "IC13") (pin "4") (pinfunction "NR_4") (pintype "passive"))
    )
    (net (code "153") (name "unconnected-(ISEL10A_1B-NO-Pad14)") (class "Default")
      (node (ref "ISEL10A_1") (pin "14") (pinfunction "NO_14") (pintype "passive"))
    )
    (net (code "154") (name "unconnected-(X2I-1-Pad17)") (class "Default")
      (node (ref "X2") (pin "17") (pinfunction "1_17") (pintype "passive"))
    )
    (net (code "155") (name "unconnected-(X2J-1-Pad18)") (class "Default")
      (node (ref "X2") (pin "18") (pinfunction "1_18") (pintype "passive"))
    )
    (net (code "156") (name "unconnected-(X3B-1-Pad10)") (class "Default")
      (node (ref "X3") (pin "10") (pinfunction "1_10") (pintype "passive"))
    )
    (net (code "157") (name "unconnected-(X3G-1-Pad15)") (class "Default")
      (node (ref "X3") (pin "15") (pinfunction "1_15") (pintype "passive"))
    )
    (net (code "158") (name "unconnected-(X3I-1-Pad17)") (class "Default")
      (node (ref "X3") (pin "17") (pinfunction "1_17") (pintype "passive"))
    )
    (net (code "159") (name "unconnected-(X3K-1-Pad19)") (class "Default")
      (node (ref "X3") (pin "19") (pinfunction "1_19") (pintype "passive"))
    )
    (net (code "160") (name "unconnected-(X3L-1-Pad2)") (class "Default")
      (node (ref "X3") (pin "2") (pinfunction "1_2") (pintype "passive"))
    )
    (net (code "161") (name "unconnected-(X3N-1-Pad21)") (class "Default")
      (node (ref "X3") (pin "21") (pinfunction "1_21") (pintype "passive"))
    )
    (net (code "162") (name "unconnected-(X3R-1-Pad25)") (class "Default")
      (node (ref "X3") (pin "25") (pinfunction "1_25") (pintype "passive"))
    )
    (net (code "163") (name "unconnected-(X3S-1-Pad26)") (class "Default")
      (node (ref "X3") (pin "26") (pinfunction "1_26") (pintype "passive"))
    )
    (net (code "164") (name "unconnected-(X3Z-1-Pad7)") (class "Default")
      (node (ref "X3") (pin "7") (pinfunction "1_7") (pintype "passive"))
    )
    (net (code "165") (name "~{ADC_CS}") (class "Default")
      (node (ref "IC11") (pin "39") (pinfunction "~{CS}_39") (pintype "input"))
      (node (ref "X2") (pin "5") (pinfunction "1_5") (pintype "passive"))
    )
    (net (code "166") (name "~{ADC_DRDY}") (class "Default")
      (node (ref "IC11") (pin "47") (pinfunction "~{DRDY}_47") (pintype "output"))
      (node (ref "X2") (pin "7") (pinfunction "1_7") (pintype "passive"))
    )
    (net (code "167") (name "~{RESET}") (class "Default")
      (node (ref "IC11") (pin "36") (pinfunction "~{RESET}_36") (pintype "input"))
      (node (ref "X2") (pin "9") (pinfunction "1_9") (pintype "passive"))
    )
  )
)
